# Driver4RackV3_9.net
KiCad netlist of a schematic drawn in Altium Designer
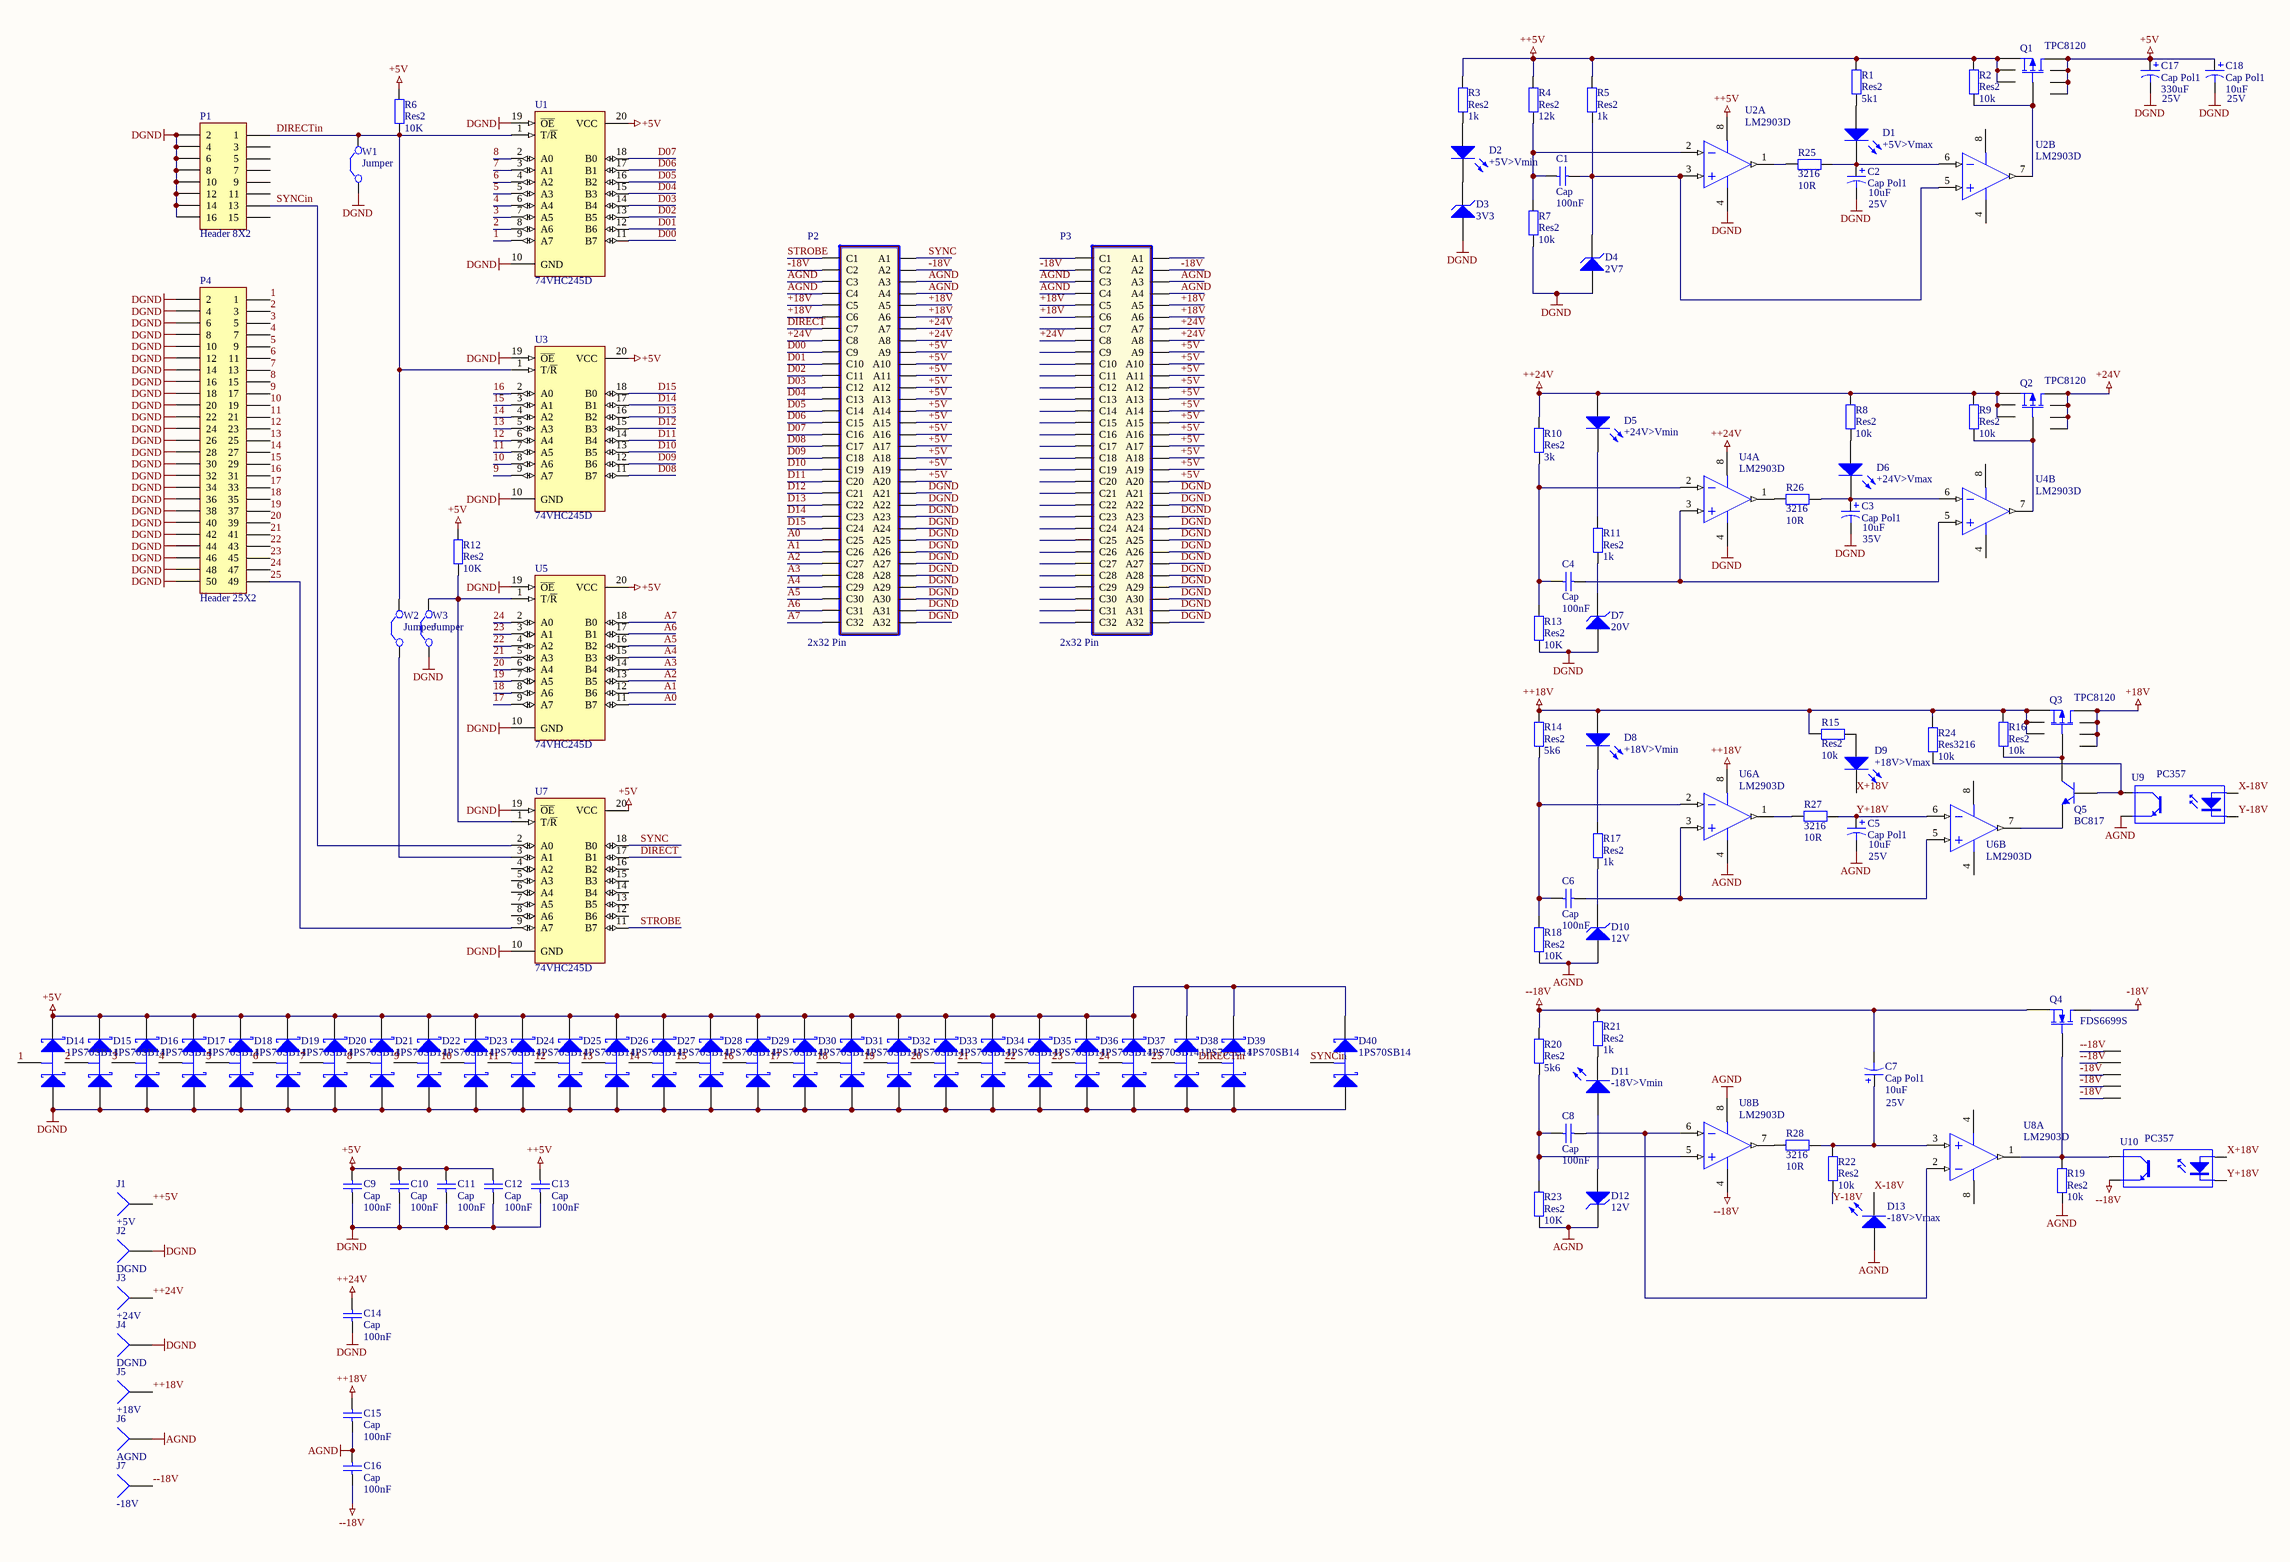
[diagram p0: Driver4RackV3.9.SchDoc]

(export (version "E")
  (design (tool "Eeschema 10.0.6"))
  (components
    (comp (ref "C1")
      (value "Cap")
      (footprint "CAPC3216M")
      (description "Capacitor")
      (fields
        (field (name "ALTIUM_VALUE") "100nF")
        (field (name "VOLTAGE") "50V")
        (field (name "PUBLISHER") "Altium Limited")
      )
      (libsource (lib "Miscellaneous Devices") (part "Cap"))
    )
    (comp (ref "C2")
      (value "Cap Pol1")
      (footprint "TC3528-1411")
      (description "Polarized Capacitor (Radial)")
      (fields
        (field (name "ALTIUM_VALUE") "10uF")
        (field (name "VOLTAGE") "25V")
        (field (name "PUBLISHER") "Altium Limited")
      )
      (libsource (lib "Miscellaneous Devices") (part "Cap Pol1"))
    )
    (comp (ref "C3")
      (value "Cap Pol1")
      (footprint "TC6032-2412")
      (description "Polarized Capacitor (Radial)")
      (fields
        (field (name "ALTIUM_VALUE") "10uF")
        (field (name "VOLTAGE") "35V")
        (field (name "PUBLISHER") "Altium Limited")
      )
      (libsource (lib "Miscellaneous Devices") (part "Cap Pol1"))
    )
    (comp (ref "C4")
      (value "Cap")
      (footprint "CAPC3216M")
      (description "Capacitor")
      (fields
        (field (name "ALTIUM_VALUE") "100nF")
        (field (name "VOLTAGE") "50V")
        (field (name "PUBLISHER") "Altium Limited")
      )
      (libsource (lib "Miscellaneous Devices") (part "Cap"))
    )
    (comp (ref "C5")
      (value "Cap Pol1")
      (footprint "TC3528-1411")
      (description "Polarized Capacitor (Radial)")
      (fields
        (field (name "ALTIUM_VALUE") "10uF")
        (field (name "VOLTAGE") "25V")
        (field (name "PUBLISHER") "Altium Limited")
      )
      (libsource (lib "Miscellaneous Devices") (part "Cap Pol1"))
    )
    (comp (ref "C6")
      (value "Cap")
      (footprint "CAPC3216M")
      (description "Capacitor")
      (fields
        (field (name "ALTIUM_VALUE") "100nF")
        (field (name "VOLTAGE") "50V")
        (field (name "PUBLISHER") "Altium Limited")
      )
      (libsource (lib "Miscellaneous Devices") (part "Cap"))
    )
    (comp (ref "C7")
      (value "Cap Pol1")
      (footprint "TC3528-1411")
      (description "Polarized Capacitor (Radial)")
      (fields
        (field (name "ALTIUM_VALUE") "10uF")
        (field (name "VOLTAGE") "25V")
        (field (name "PUBLISHER") "Altium Limited")
      )
      (libsource (lib "Miscellaneous Devices") (part "Cap Pol1"))
    )
    (comp (ref "C8")
      (value "Cap")
      (footprint "CAPC3216M")
      (description "Capacitor")
      (fields
        (field (name "ALTIUM_VALUE") "100nF")
        (field (name "VOLTAGE") "50V")
        (field (name "PUBLISHER") "Altium Limited")
      )
      (libsource (lib "Miscellaneous Devices") (part "Cap"))
    )
    (comp (ref "C9")
      (value "Cap")
      (footprint "CAPC3216M")
      (description "Capacitor")
      (fields
        (field (name "ALTIUM_VALUE") "100nF")
        (field (name "VOLTAGE") "50V")
        (field (name "PUBLISHER") "Altium Limited")
      )
      (libsource (lib "Miscellaneous Devices") (part "Cap"))
    )
    (comp (ref "C10")
      (value "Cap")
      (footprint "CAPC3216M")
      (description "Capacitor")
      (fields
        (field (name "ALTIUM_VALUE") "100nF")
        (field (name "VOLTAGE") "50V")
        (field (name "PUBLISHER") "Altium Limited")
      )
      (libsource (lib "Miscellaneous Devices") (part "Cap"))
    )
    (comp (ref "C11")
      (value "Cap")
      (footprint "CAPC3216M")
      (description "Capacitor")
      (fields
        (field (name "ALTIUM_VALUE") "100nF")
        (field (name "VOLTAGE") "50V")
        (field (name "PUBLISHER") "Altium Limited")
      )
      (libsource (lib "Miscellaneous Devices") (part "Cap"))
    )
    (comp (ref "C12")
      (value "Cap")
      (footprint "CAPC3216M")
      (description "Capacitor")
      (fields
        (field (name "ALTIUM_VALUE") "100nF")
        (field (name "VOLTAGE") "50V")
        (field (name "PUBLISHER") "Altium Limited")
      )
      (libsource (lib "Miscellaneous Devices") (part "Cap"))
    )
    (comp (ref "C13")
      (value "Cap")
      (footprint "CAPC3216M")
      (description "Capacitor")
      (fields
        (field (name "ALTIUM_VALUE") "100nF")
        (field (name "VOLTAGE") "50V")
        (field (name "PUBLISHER") "Altium Limited")
      )
      (libsource (lib "Miscellaneous Devices") (part "Cap"))
    )
    (comp (ref "C14")
      (value "Cap")
      (footprint "CAPC3216M")
      (description "Capacitor")
      (fields
        (field (name "ALTIUM_VALUE") "100nF")
        (field (name "VOLTAGE") "50V")
        (field (name "PUBLISHER") "Altium Limited")
      )
      (libsource (lib "Miscellaneous Devices") (part "Cap"))
    )
    (comp (ref "C15")
      (value "Cap")
      (footprint "CAPC3216M")
      (description "Capacitor")
      (fields
        (field (name "ALTIUM_VALUE") "100nF")
        (field (name "VOLTAGE") "50V")
        (field (name "PUBLISHER") "Altium Limited")
      )
      (libsource (lib "Miscellaneous Devices") (part "Cap"))
    )
    (comp (ref "C16")
      (value "Cap")
      (footprint "CAPC3216M")
      (description "Capacitor")
      (fields
        (field (name "ALTIUM_VALUE") "100nF")
        (field (name "VOLTAGE") "50V")
        (field (name "PUBLISHER") "Altium Limited")
      )
      (libsource (lib "Miscellaneous Devices") (part "Cap"))
    )
    (comp (ref "C17")
      (value "Cap Pol1")
      (footprint "ElkoSMD8")
      (description "Polarized Capacitor (Radial)")
      (fields
        (field (name "ALTIUM_VALUE") "330uF")
        (field (name "VOLTAGE") "25V")
        (field (name "PUBLISHER") "Altium Limited")
      )
      (libsource (lib "Miscellaneous Devices") (part "Cap Pol1"))
    )
    (comp (ref "C18")
      (value "Cap Pol1")
      (footprint "TC3528-1411")
      (description "Polarized Capacitor (Radial)")
      (fields
        (field (name "ALTIUM_VALUE") "10uF")
        (field (name "VOLTAGE") "25V")
        (field (name "PUBLISHER") "Altium Limited")
      )
      (libsource (lib "Miscellaneous Devices") (part "Cap Pol1"))
    )
    (comp (ref "D1")
      (value "+5V>Vmax")
      (footprint "3.5X2.8X1.9")
      (description "Typical RED GaAs LED")
      (fields (field (name "PUBLISHER") "Altium Limited"))
      (libsource (lib "Miscellaneous Devices") (part "LED1"))
    )
    (comp (ref "D2")
      (value "+5V>Vmin")
      (footprint "3.5X2.8X1.9")
      (description "Typical green SiC LED")
      (fields (field (name "PUBLISHER") "Altium Limited"))
      (libsource (lib "Miscellaneous Devices") (part "LED3"))
    )
    (comp (ref "D3")
      (value "3V3")
      (footprint "sod80c")
      (description "Zener Diode")
      (fields (field (name "PUBLISHER") "Altium Limited"))
      (libsource (lib "Miscellaneous Devices") (part "D Zener"))
    )
    (comp (ref "D4")
      (value "2V7")
      (footprint "sod80c")
      (description "Zener Diode")
      (fields (field (name "PUBLISHER") "Altium Limited"))
      (libsource (lib "Miscellaneous Devices") (part "D Zener"))
    )
    (comp (ref "D5")
      (value "+24V>Vmin")
      (footprint "3.5X2.8X1.9")
      (description "Typical green GaAs LED")
      (fields (field (name "PUBLISHER") "Altium Limited"))
      (libsource (lib "Miscellaneous Devices") (part "LED1"))
    )
    (comp (ref "D6")
      (value "+24V>Vmax")
      (footprint "3.5X2.8X1.9")
      (description "Typical RED GaAs LED")
      (fields (field (name "PUBLISHER") "Altium Limited"))
      (libsource (lib "Miscellaneous Devices") (part "LED1"))
    )
    (comp (ref "D7")
      (value "20V")
      (footprint "sod80c")
      (description "Zener Diode")
      (fields (field (name "PUBLISHER") "Altium Limited"))
      (libsource (lib "Miscellaneous Devices") (part "D Zener"))
    )
    (comp (ref "D8")
      (value "+18V>Vmin")
      (footprint "3.5X2.8X1.9")
      (description "Typical green GaAs LED")
      (fields (field (name "PUBLISHER") "Altium Limited"))
      (libsource (lib "Miscellaneous Devices") (part "LED1"))
    )
    (comp (ref "D9")
      (value "+18V>Vmax")
      (footprint "3.5X2.8X1.9")
      (description "Typical RED GaAs LED")
      (fields (field (name "PUBLISHER") "Altium Limited"))
      (libsource (lib "Miscellaneous Devices") (part "LED1"))
    )
    (comp (ref "D10")
      (value "12V")
      (footprint "sod80c")
      (description "Zener Diode")
      (fields (field (name "PUBLISHER") "Altium Limited"))
      (libsource (lib "Miscellaneous Devices") (part "D Zener"))
    )
    (comp (ref "D11")
      (value "-18V>Vmin")
      (footprint "3.5X2.8X1.9")
      (description "Typical green GaAs LED")
      (fields (field (name "PUBLISHER") "Altium Limited"))
      (libsource (lib "Miscellaneous Devices") (part "LED1"))
    )
    (comp (ref "D12")
      (value "12V")
      (footprint "sod80c")
      (description "Zener Diode")
      (fields (field (name "PUBLISHER") "Altium Limited"))
      (libsource (lib "Miscellaneous Devices") (part "D Zener"))
    )
    (comp (ref "D13")
      (value "-18V>Vmax")
      (footprint "3.5X2.8X1.9")
      (description "Typical RED GaAs LED")
      (fields (field (name "PUBLISHER") "Altium Limited"))
      (libsource (lib "Miscellaneous Devices") (part "LED1"))
    )
    (comp (ref "D14")
      (value "1PS70SB14")
      (footprint "SOT323")
      (description "Schottky Barrier Double Diode")
      (fields (field (name "PUBLISHER") "Altium Limited"))
      (libsource (lib "Philips Discrete Diode - Schottky") (part "1PS70SB14"))
    )
    (comp (ref "D15")
      (value "1PS70SB14")
      (footprint "SOT323")
      (description "Schottky Barrier Double Diode")
      (fields (field (name "PUBLISHER") "Altium Limited"))
      (libsource (lib "Philips Discrete Diode - Schottky") (part "1PS70SB14"))
    )
    (comp (ref "D16")
      (value "1PS70SB14")
      (footprint "SOT323")
      (description "Schottky Barrier Double Diode")
      (fields (field (name "PUBLISHER") "Altium Limited"))
      (libsource (lib "Philips Discrete Diode - Schottky") (part "1PS70SB14"))
    )
    (comp (ref "D17")
      (value "1PS70SB14")
      (footprint "SOT323")
      (description "Schottky Barrier Double Diode")
      (fields (field (name "PUBLISHER") "Altium Limited"))
      (libsource (lib "Philips Discrete Diode - Schottky") (part "1PS70SB14"))
    )
    (comp (ref "D18")
      (value "1PS70SB14")
      (footprint "SOT323")
      (description "Schottky Barrier Double Diode")
      (fields (field (name "PUBLISHER") "Altium Limited"))
      (libsource (lib "Philips Discrete Diode - Schottky") (part "1PS70SB14"))
    )
    (comp (ref "D19")
      (value "1PS70SB14")
      (footprint "SOT323")
      (description "Schottky Barrier Double Diode")
      (fields (field (name "PUBLISHER") "Altium Limited"))
      (libsource (lib "Philips Discrete Diode - Schottky") (part "1PS70SB14"))
    )
    (comp (ref "D20")
      (value "1PS70SB14")
      (footprint "SOT323")
      (description "Schottky Barrier Double Diode")
      (fields (field (name "PUBLISHER") "Altium Limited"))
      (libsource (lib "Philips Discrete Diode - Schottky") (part "1PS70SB14"))
    )
    (comp (ref "D21")
      (value "1PS70SB14")
      (footprint "SOT323")
      (description "Schottky Barrier Double Diode")
      (fields (field (name "PUBLISHER") "Altium Limited"))
      (libsource (lib "Philips Discrete Diode - Schottky") (part "1PS70SB14"))
    )
    (comp (ref "D22")
      (value "1PS70SB14")
      (footprint "SOT323")
      (description "Schottky Barrier Double Diode")
      (fields (field (name "PUBLISHER") "Altium Limited"))
      (libsource (lib "Philips Discrete Diode - Schottky") (part "1PS70SB14"))
    )
    (comp (ref "D23")
      (value "1PS70SB14")
      (footprint "SOT323")
      (description "Schottky Barrier Double Diode")
      (fields (field (name "PUBLISHER") "Altium Limited"))
      (libsource (lib "Philips Discrete Diode - Schottky") (part "1PS70SB14"))
    )
    (comp (ref "D24")
      (value "1PS70SB14")
      (footprint "SOT323")
      (description "Schottky Barrier Double Diode")
      (fields (field (name "PUBLISHER") "Altium Limited"))
      (libsource (lib "Philips Discrete Diode - Schottky") (part "1PS70SB14"))
    )
    (comp (ref "D25")
      (value "1PS70SB14")
      (footprint "SOT323")
      (description "Schottky Barrier Double Diode")
      (fields (field (name "PUBLISHER") "Altium Limited"))
      (libsource (lib "Philips Discrete Diode - Schottky") (part "1PS70SB14"))
    )
    (comp (ref "D26")
      (value "1PS70SB14")
      (footprint "SOT323")
      (description "Schottky Barrier Double Diode")
      (fields (field (name "PUBLISHER") "Altium Limited"))
      (libsource (lib "Philips Discrete Diode - Schottky") (part "1PS70SB14"))
    )
    (comp (ref "D27")
      (value "1PS70SB14")
      (footprint "SOT323")
      (description "Schottky Barrier Double Diode")
      (fields (field (name "PUBLISHER") "Altium Limited"))
      (libsource (lib "Philips Discrete Diode - Schottky") (part "1PS70SB14"))
    )
    (comp (ref "D28")
      (value "1PS70SB14")
      (footprint "SOT323")
      (description "Schottky Barrier Double Diode")
      (fields (field (name "PUBLISHER") "Altium Limited"))
      (libsource (lib "Philips Discrete Diode - Schottky") (part "1PS70SB14"))
    )
    (comp (ref "D29")
      (value "1PS70SB14")
      (footprint "SOT323")
      (description "Schottky Barrier Double Diode")
      (fields (field (name "PUBLISHER") "Altium Limited"))
      (libsource (lib "Philips Discrete Diode - Schottky") (part "1PS70SB14"))
    )
    (comp (ref "D30")
      (value "1PS70SB14")
      (footprint "SOT323")
      (description "Schottky Barrier Double Diode")
      (fields (field (name "PUBLISHER") "Altium Limited"))
      (libsource (lib "Philips Discrete Diode - Schottky") (part "1PS70SB14"))
    )
    (comp (ref "D31")
      (value "1PS70SB14")
      (footprint "SOT323")
      (description "Schottky Barrier Double Diode")
      (fields (field (name "PUBLISHER") "Altium Limited"))
      (libsource (lib "Philips Discrete Diode - Schottky") (part "1PS70SB14"))
    )
    (comp (ref "D32")
      (value "1PS70SB14")
      (footprint "SOT323")
      (description "Schottky Barrier Double Diode")
      (fields (field (name "PUBLISHER") "Altium Limited"))
      (libsource (lib "Philips Discrete Diode - Schottky") (part "1PS70SB14"))
    )
    (comp (ref "D33")
      (value "1PS70SB14")
      (footprint "SOT323")
      (description "Schottky Barrier Double Diode")
      (fields (field (name "PUBLISHER") "Altium Limited"))
      (libsource (lib "Philips Discrete Diode - Schottky") (part "1PS70SB14"))
    )
    (comp (ref "D34")
      (value "1PS70SB14")
      (footprint "SOT323")
      (description "Schottky Barrier Double Diode")
      (fields (field (name "PUBLISHER") "Altium Limited"))
      (libsource (lib "Philips Discrete Diode - Schottky") (part "1PS70SB14"))
    )
    (comp (ref "D35")
      (value "1PS70SB14")
      (footprint "SOT323")
      (description "Schottky Barrier Double Diode")
      (fields (field (name "PUBLISHER") "Altium Limited"))
      (libsource (lib "Philips Discrete Diode - Schottky") (part "1PS70SB14"))
    )
    (comp (ref "D36")
      (value "1PS70SB14")
      (footprint "SOT323")
      (description "Schottky Barrier Double Diode")
      (fields (field (name "PUBLISHER") "Altium Limited"))
      (libsource (lib "Philips Discrete Diode - Schottky") (part "1PS70SB14"))
    )
    (comp (ref "D37")
      (value "1PS70SB14")
      (footprint "SOT323")
      (description "Schottky Barrier Double Diode")
      (fields (field (name "PUBLISHER") "Altium Limited"))
      (libsource (lib "Philips Discrete Diode - Schottky") (part "1PS70SB14"))
    )
    (comp (ref "D38")
      (value "1PS70SB14")
      (footprint "SOT323")
      (description "Schottky Barrier Double Diode")
      (fields (field (name "PUBLISHER") "Altium Limited"))
      (libsource (lib "Philips Discrete Diode - Schottky") (part "1PS70SB14"))
    )
    (comp (ref "D39")
      (value "1PS70SB14")
      (footprint "SOT323")
      (description "Schottky Barrier Double Diode")
      (fields (field (name "PUBLISHER") "Altium Limited"))
      (libsource (lib "Philips Discrete Diode - Schottky") (part "1PS70SB14"))
    )
    (comp (ref "D40")
      (value "1PS70SB14")
      (footprint "SOT323")
      (description "Schottky Barrier Double Diode")
      (fields (field (name "PUBLISHER") "Altium Limited"))
      (libsource (lib "Philips Discrete Diode - Schottky") (part "1PS70SB14"))
    )
    (comp (ref "J1")
      (value "+5V")
      (footprint "PIN1")
      (description "Socket")
      (fields (field (name "PUBLISHER") "Altium Limited"))
      (libsource (lib "Miscellaneous Connectors") (part "Socket"))
    )
    (comp (ref "J2")
      (value "DGND")
      (footprint "PIN1")
      (description "Socket")
      (fields (field (name "PUBLISHER") "Altium Limited"))
      (libsource (lib "Miscellaneous Connectors") (part "Socket"))
    )
    (comp (ref "J3")
      (value "+24V")
      (footprint "PIN1")
      (description "Socket")
      (fields (field (name "PUBLISHER") "Altium Limited"))
      (libsource (lib "Miscellaneous Connectors") (part "Socket"))
    )
    (comp (ref "J4")
      (value "DGND")
      (footprint "PIN1")
      (description "Socket")
      (fields (field (name "PUBLISHER") "Altium Limited"))
      (libsource (lib "Miscellaneous Connectors") (part "Socket"))
    )
    (comp (ref "J5")
      (value "+18V")
      (footprint "PIN1")
      (description "Socket")
      (fields (field (name "PUBLISHER") "Altium Limited"))
      (libsource (lib "Miscellaneous Connectors") (part "Socket"))
    )
    (comp (ref "J6")
      (value "AGND")
      (footprint "PIN1")
      (description "Socket")
      (fields (field (name "PUBLISHER") "Altium Limited"))
      (libsource (lib "Miscellaneous Connectors") (part "Socket"))
    )
    (comp (ref "J7")
      (value "-18V")
      (footprint "PIN1")
      (description "Socket")
      (fields (field (name "PUBLISHER") "Altium Limited"))
      (libsource (lib "Miscellaneous Connectors") (part "Socket"))
    )
    (comp (ref "P1")
      (value "Header 8X2")
      (footprint "HDR2X8")
      (description "Header, 8-Pin, Dual row")
      (fields (field (name "PUBLISHER") "Altium Limited"))
      (libsource (lib "Miscellaneous Connectors") (part "Header 8X2"))
    )
    (comp (ref "P2")
      (value "2x32 Pin")
      (footprint "0903164x922")
      (description "DIN 41612")
      (libsource (lib "GeneralParts") (part "64 Pin Header"))
    )
    (comp (ref "P3")
      (value "2x32 Pin")
      (footprint "0903164x922")
      (description "DIN 41612")
      (libsource (lib "GeneralParts") (part "64 Pin Header"))
    )
    (comp (ref "P4")
      (value "Header 25X2")
      (footprint "HDR2X25")
      (description "Header, 25-Pin, Dual row")
      (fields (field (name "PUBLISHER") "Altium Limited"))
      (libsource (lib "Miscellaneous Connectors") (part "Header 25X2"))
    )
    (comp (ref "Q1")
      (value "TPC8120")
      (footprint "2-6J1B")
      (description "Mosfet P")
      (libsource (lib "eigene") (part "TPC8120"))
    )
    (comp (ref "Q2")
      (value "TPC8120")
      (footprint "2-6J1B")
      (description "Mosfet P")
      (libsource (lib "eigene") (part "TPC8120"))
    )
    (comp (ref "Q3")
      (value "TPC8120")
      (footprint "2-6J1B")
      (description "Mosfet P")
      (libsource (lib "eigene") (part "TPC8120"))
    )
    (comp (ref "Q4")
      (value "FDS6699S")
      (footprint "SO-8_M")
      (description "N-Channel MOSFET")
      (fields (field (name "PUBLISHER") "Altium Limited"))
      (libsource (lib "Miscellaneous Devices") (part "MOSFET-N"))
    )
    (comp (ref "Q5")
      (value "BC817")
      (footprint "SOT-23B_N")
      (description "NPN Bipolar Transistor")
      (fields (field (name "PUBLISHER") "Altium Limited"))
      (libsource (lib "Miscellaneous Devices") (part "QNPN"))
    )
    (comp (ref "R1")
      (value "Res2")
      (footprint "RESC3216M")
      (description "Resistor")
      (fields (field (name "ALTIUM_VALUE") "5k1") (field (name "PUBLISHER") "Altium Limited"))
      (libsource (lib "Miscellaneous Devices") (part "Res2"))
    )
    (comp (ref "R2")
      (value "Res2")
      (footprint "RESC3216M")
      (description "Resistor")
      (fields (field (name "ALTIUM_VALUE") "10k") (field (name "PUBLISHER") "Altium Limited"))
      (libsource (lib "Miscellaneous Devices") (part "Res2"))
    )
    (comp (ref "R3")
      (value "Res2")
      (footprint "RESC3216M")
      (description "Resistor")
      (fields (field (name "ALTIUM_VALUE") "1k") (field (name "PUBLISHER") "Altium Limited"))
      (libsource (lib "Miscellaneous Devices") (part "Res2"))
    )
    (comp (ref "R4")
      (value "Res2")
      (footprint "RESC3216M")
      (description "Resistor")
      (fields (field (name "ALTIUM_VALUE") "12k") (field (name "PUBLISHER") "Altium Limited"))
      (libsource (lib "Miscellaneous Devices") (part "Res2"))
    )
    (comp (ref "R5")
      (value "Res2")
      (footprint "RESC3216M")
      (description "Resistor")
      (fields (field (name "ALTIUM_VALUE") "1k") (field (name "PUBLISHER") "Altium Limited"))
      (libsource (lib "Miscellaneous Devices") (part "Res2"))
    )
    (comp (ref "R6")
      (value "Res2")
      (footprint "RESC3216M")
      (description "Resistor")
      (fields (field (name "ALTIUM_VALUE") "10K") (field (name "PUBLISHER") "Altium Limited"))
      (libsource (lib "") (part "Res2_1"))
    )
    (comp (ref "R7")
      (value "Res2")
      (footprint "RESC3216M")
      (description "Resistor")
      (fields (field (name "ALTIUM_VALUE") "10k") (field (name "PUBLISHER") "Altium Limited"))
      (libsource (lib "Miscellaneous Devices") (part "Res2"))
    )
    (comp (ref "R8")
      (value "Res2")
      (footprint "RESC3216M")
      (description "Resistor")
      (fields (field (name "ALTIUM_VALUE") "10k") (field (name "PUBLISHER") "Altium Limited"))
      (libsource (lib "Miscellaneous Devices") (part "Res2"))
    )
    (comp (ref "R9")
      (value "Res2")
      (footprint "RESC3216M")
      (description "Resistor")
      (fields (field (name "ALTIUM_VALUE") "10k") (field (name "PUBLISHER") "Altium Limited"))
      (libsource (lib "Miscellaneous Devices") (part "Res2"))
    )
    (comp (ref "R10")
      (value "Res2")
      (footprint "RESC3216M")
      (description "Resistor")
      (fields (field (name "ALTIUM_VALUE") "3k") (field (name "PUBLISHER") "Altium Limited"))
      (libsource (lib "Miscellaneous Devices") (part "Res2"))
    )
    (comp (ref "R11")
      (value "Res2")
      (footprint "RESC3216M")
      (description "Resistor")
      (fields (field (name "ALTIUM_VALUE") "1k") (field (name "PUBLISHER") "Altium Limited"))
      (libsource (lib "Miscellaneous Devices") (part "Res2"))
    )
    (comp (ref "R12")
      (value "Res2")
      (footprint "RESC3216M")
      (description "Resistor")
      (fields (field (name "ALTIUM_VALUE") "10K") (field (name "PUBLISHER") "Altium Limited"))
      (libsource (lib "") (part "Res2_1"))
    )
    (comp (ref "R13")
      (value "Res2")
      (footprint "RESC3216M")
      (description "Resistor")
      (fields (field (name "ALTIUM_VALUE") "10K") (field (name "PUBLISHER") "Altium Limited"))
      (libsource (lib "Miscellaneous Devices") (part "Res2"))
    )
    (comp (ref "R14")
      (value "Res2")
      (footprint "RESC3216M")
      (description "Resistor")
      (fields (field (name "ALTIUM_VALUE") "5k6") (field (name "PUBLISHER") "Altium Limited"))
      (libsource (lib "Miscellaneous Devices") (part "Res2"))
    )
    (comp (ref "R15")
      (value "Res2")
      (footprint "RESC3216M")
      (description "Resistor")
      (fields (field (name "ALTIUM_VALUE") "10k") (field (name "PUBLISHER") "Altium Limited"))
      (libsource (lib "") (part "Res2_2"))
    )
    (comp (ref "R16")
      (value "Res2")
      (footprint "RESC3216M")
      (description "Resistor")
      (fields (field (name "ALTIUM_VALUE") "10k") (field (name "PUBLISHER") "Altium Limited"))
      (libsource (lib "Miscellaneous Devices") (part "Res2"))
    )
    (comp (ref "R17")
      (value "Res2")
      (footprint "RESC3216M")
      (description "Resistor")
      (fields (field (name "ALTIUM_VALUE") "1k") (field (name "PUBLISHER") "Altium Limited"))
      (libsource (lib "") (part "Res2_3"))
    )
    (comp (ref "R18")
      (value "Res2")
      (footprint "RESC3216M")
      (description "Resistor")
      (fields (field (name "ALTIUM_VALUE") "10K") (field (name "PUBLISHER") "Altium Limited"))
      (libsource (lib "Miscellaneous Devices") (part "Res2"))
    )
    (comp (ref "R19")
      (value "Res2")
      (footprint "RESC3216M")
      (description "Resistor")
      (fields (field (name "ALTIUM_VALUE") "10k") (field (name "PUBLISHER") "Altium Limited"))
      (libsource (lib "Miscellaneous Devices") (part "Res2"))
    )
    (comp (ref "R20")
      (value "Res2")
      (footprint "RESC3216M")
      (description "Resistor")
      (fields (field (name "ALTIUM_VALUE") "5k6") (field (name "PUBLISHER") "Altium Limited"))
      (libsource (lib "Miscellaneous Devices") (part "Res2"))
    )
    (comp (ref "R21")
      (value "Res2")
      (footprint "RESC3216M")
      (description "Resistor")
      (fields (field (name "ALTIUM_VALUE") "1k") (field (name "PUBLISHER") "Altium Limited"))
      (libsource (lib "") (part "Res2_3"))
    )
    (comp (ref "R22")
      (value "Res2")
      (footprint "RESC3216M")
      (description "Resistor")
      (fields (field (name "ALTIUM_VALUE") "10k") (field (name "PUBLISHER") "Altium Limited"))
      (libsource (lib "Miscellaneous Devices") (part "Res2"))
    )
    (comp (ref "R23")
      (value "Res2")
      (footprint "RESC3216M")
      (description "Resistor")
      (fields (field (name "ALTIUM_VALUE") "10K") (field (name "PUBLISHER") "Altium Limited"))
      (libsource (lib "Miscellaneous Devices") (part "Res2"))
    )
    (comp (ref "R24")
      (value "Res3216")
      (footprint "RESC3216M")
      (description "Resistor")
      (fields (field (name "ALTIUM_VALUE") "10k") (field (name "PUBLISHER") "Altium Limited"))
      (libsource (lib "") (part "Resistor3216_1"))
    )
    (comp (ref "R25")
      (value "3216")
      (footprint "RESC3216M")
      (description "Resistor")
      (fields (field (name "ALTIUM_VALUE") "10R") (field (name "PUBLISHER") "Altium Limited"))
      (libsource (lib "eigene") (part "Resistor3216"))
    )
    (comp (ref "R26")
      (value "3216")
      (footprint "RESC3216M")
      (description "Resistor")
      (fields (field (name "ALTIUM_VALUE") "10R") (field (name "PUBLISHER") "Altium Limited"))
      (libsource (lib "eigene") (part "Resistor3216"))
    )
    (comp (ref "R27")
      (value "3216")
      (footprint "RESC3216M")
      (description "Resistor")
      (fields (field (name "ALTIUM_VALUE") "10R") (field (name "PUBLISHER") "Altium Limited"))
      (libsource (lib "eigene") (part "Resistor3216"))
    )
    (comp (ref "R28")
      (value "3216")
      (footprint "RESC3216M")
      (description "Resistor")
      (fields (field (name "ALTIUM_VALUE") "10R") (field (name "PUBLISHER") "Altium Limited"))
      (libsource (lib "eigene") (part "Resistor3216"))
    )
    (comp (ref "U1")
      (value "74VHC245D")
      (footprint "DW020_N")
      (description "Octal Bus Transceiver with 3-State Outputs")
      (fields (field (name "PUBLISHER") "Altium Limited"))
      (libsource (lib "TI Interface 8-Bit Line Transceiver") (part "SN74HC245DW"))
    )
    (comp (ref "U2")
      (value "LM2903D")
      (footprint "751-02_N")
      (description "Dual Comparator")
      (fields (field (name "PUBLISHER") "Altium Limited"))
      (libsource (lib "Motorola Analog Comparator") (part "LM2903D"))
    )
    (comp (ref "U3")
      (value "74VHC245D")
      (footprint "DW020_N")
      (description "Octal Bus Transceiver with 3-State Outputs")
      (fields (field (name "PUBLISHER") "Altium Limited"))
      (libsource (lib "TI Interface 8-Bit Line Transceiver") (part "SN74HC245DW"))
    )
    (comp (ref "U4")
      (value "LM2903D")
      (footprint "751-02_N")
      (description "Dual Comparator")
      (fields (field (name "PUBLISHER") "Altium Limited"))
      (libsource (lib "Motorola Analog Comparator") (part "LM2903D"))
    )
    (comp (ref "U5")
      (value "74VHC245D")
      (footprint "DW020_N")
      (description "Octal Bus Transceiver with 3-State Outputs")
      (fields (field (name "PUBLISHER") "Altium Limited"))
      (libsource (lib "TI Interface 8-Bit Line Transceiver") (part "SN74HC245DW"))
    )
    (comp (ref "U6")
      (value "LM2903D")
      (footprint "751-02_N")
      (description "Dual Comparator")
      (fields (field (name "PUBLISHER") "Altium Limited"))
      (libsource (lib "Motorola Analog Comparator") (part "LM2903D"))
    )
    (comp (ref "U7")
      (value "74VHC245D")
      (footprint "DW020_N")
      (description "Octal Bus Transceiver with 3-State Outputs")
      (fields (field (name "PUBLISHER") "Altium Limited"))
      (libsource (lib "TI Interface 8-Bit Line Transceiver") (part "SN74HC245DW"))
    )
    (comp (ref "U8")
      (value "LM2903D")
      (footprint "751-02_N")
      (description "Dual Comparator")
      (fields (field (name "PUBLISHER") "Altium Limited"))
      (libsource (lib "Motorola Analog Comparator") (part "LM2903D"))
    )
    (comp (ref "U9")
      (value "PC357")
      (footprint "PC357NJ")
      (description "4-Pin Phototransistor Optocoupler")
      (fields (field (name "PUBLISHER") "Altium Limited"))
      (libsource (lib "Miscellaneous Devices") (part "Optoisolator1"))
    )
    (comp (ref "U10")
      (value "PC357")
      (footprint "PC357NJ")
      (description "4-Pin Phototransistor Optocoupler")
      (fields (field (name "PUBLISHER") "Altium Limited"))
      (libsource (lib "Miscellaneous Devices") (part "Optoisolator1"))
    )
    (comp (ref "W1")
      (value "Jumper")
      (footprint "RAD-0.1")
      (description "Jumper Wire")
      (fields (field (name "PUBLISHER") "Altium Limited"))
      (libsource (lib "Miscellaneous Devices") (part "Jumper"))
    )
    (comp (ref "W2")
      (value "Jumper")
      (footprint "RAD-0.1")
      (description "Jumper Wire")
      (fields (field (name "PUBLISHER") "Altium Limited"))
      (libsource (lib "Miscellaneous Devices") (part "Jumper"))
    )
    (comp (ref "W3")
      (value "Jumper")
      (footprint "RAD-0.1")
      (description "Jumper Wire")
      (fields (field (name "PUBLISHER") "Altium Limited"))
      (libsource (lib "Miscellaneous Devices") (part "Jumper"))
    )
  )
  (nets
    (net (code "1") (name "++5V") (class "Default")
      (node (ref "C13") (pin "2") (pinfunction "2_2") (pintype "passive"))
      (node (ref "J1") (pin "1") (pinfunction "1_1") (pintype "passive"))
      (node (ref "Q1") (pin "1") (pinfunction "S_1") (pintype "passive"))
      (node (ref "Q1") (pin "2") (pinfunction "S_2") (pintype "passive"))
      (node (ref "Q1") (pin "3") (pinfunction "S_3") (pintype "passive"))
      (node (ref "R1") (pin "2") (pinfunction "2_2") (pintype "passive"))
      (node (ref "R2") (pin "2") (pinfunction "2_2") (pintype "passive"))
      (node (ref "R3") (pin "2") (pinfunction "2_2") (pintype "passive"))
      (node (ref "R4") (pin "2") (pinfunction "2_2") (pintype "passive"))
      (node (ref "R5") (pin "2") (pinfunction "2_2") (pintype "passive"))
      (node (ref "U2") (pin "8") (pinfunction "V+_8") (pintype "power_in"))
    )
    (net (code "2") (name "++18V") (class "Default")
      (node (ref "C15") (pin "2") (pinfunction "2_2") (pintype "passive"))
      (node (ref "D8") (pin "1") (pinfunction "A_1") (pintype "passive"))
      (node (ref "J5") (pin "1") (pinfunction "1_1") (pintype "passive"))
      (node (ref "Q3") (pin "1") (pinfunction "S_1") (pintype "passive"))
      (node (ref "Q3") (pin "2") (pinfunction "S_2") (pintype "passive"))
      (node (ref "Q3") (pin "3") (pinfunction "S_3") (pintype "passive"))
      (node (ref "R14") (pin "2") (pinfunction "2_2") (pintype "passive"))
      (node (ref "R15") (pin "2") (pinfunction "2_2") (pintype "passive"))
      (node (ref "R16") (pin "2") (pinfunction "2_2") (pintype "passive"))
      (node (ref "R24") (pin "1") (pinfunction "1_1") (pintype "passive"))
      (node (ref "U6") (pin "8") (pinfunction "V+_8") (pintype "power_in"))
    )
    (net (code "3") (name "++24V") (class "Default")
      (node (ref "C14") (pin "2") (pinfunction "2_2") (pintype "passive"))
      (node (ref "D5") (pin "1") (pinfunction "A_1") (pintype "passive"))
      (node (ref "J3") (pin "1") (pinfunction "1_1") (pintype "passive"))
      (node (ref "Q2") (pin "1") (pinfunction "S_1") (pintype "passive"))
      (node (ref "Q2") (pin "2") (pinfunction "S_2") (pintype "passive"))
      (node (ref "Q2") (pin "3") (pinfunction "S_3") (pintype "passive"))
      (node (ref "R10") (pin "2") (pinfunction "2_2") (pintype "passive"))
      (node (ref "R8") (pin "2") (pinfunction "2_2") (pintype "passive"))
      (node (ref "R9") (pin "2") (pinfunction "2_2") (pintype "passive"))
      (node (ref "U4") (pin "8") (pinfunction "V+_8") (pintype "power_in"))
    )
    (net (code "4") (name "+5V") (class "Default")
      (node (ref "C10") (pin "2") (pinfunction "2_2") (pintype "passive"))
      (node (ref "C11") (pin "2") (pinfunction "2_2") (pintype "passive"))
      (node (ref "C12") (pin "2") (pinfunction "2_2") (pintype "passive"))
      (node (ref "C17") (pin "1") (pinfunction "1_1") (pintype "passive"))
      (node (ref "C18") (pin "1") (pinfunction "1_1") (pintype "passive"))
      (node (ref "C9") (pin "2") (pinfunction "2_2") (pintype "passive"))
      (node (ref "D14") (pin "2") (pinfunction "K_2") (pintype "passive"))
      (node (ref "D15") (pin "2") (pinfunction "K_2") (pintype "passive"))
      (node (ref "D16") (pin "2") (pinfunction "K_2") (pintype "passive"))
      (node (ref "D17") (pin "2") (pinfunction "K_2") (pintype "passive"))
      (node (ref "D18") (pin "2") (pinfunction "K_2") (pintype "passive"))
      (node (ref "D19") (pin "2") (pinfunction "K_2") (pintype "passive"))
      (node (ref "D20") (pin "2") (pinfunction "K_2") (pintype "passive"))
      (node (ref "D21") (pin "2") (pinfunction "K_2") (pintype "passive"))
      (node (ref "D22") (pin "2") (pinfunction "K_2") (pintype "passive"))
      (node (ref "D23") (pin "2") (pinfunction "K_2") (pintype "passive"))
      (node (ref "D24") (pin "2") (pinfunction "K_2") (pintype "passive"))
      (node (ref "D25") (pin "2") (pinfunction "K_2") (pintype "passive"))
      (node (ref "D26") (pin "2") (pinfunction "K_2") (pintype "passive"))
      (node (ref "D27") (pin "2") (pinfunction "K_2") (pintype "passive"))
      (node (ref "D28") (pin "2") (pinfunction "K_2") (pintype "passive"))
      (node (ref "D29") (pin "2") (pinfunction "K_2") (pintype "passive"))
      (node (ref "D30") (pin "2") (pinfunction "K_2") (pintype "passive"))
      (node (ref "D31") (pin "2") (pinfunction "K_2") (pintype "passive"))
      (node (ref "D32") (pin "2") (pinfunction "K_2") (pintype "passive"))
      (node (ref "D33") (pin "2") (pinfunction "K_2") (pintype "passive"))
      (node (ref "D34") (pin "2") (pinfunction "K_2") (pintype "passive"))
      (node (ref "D35") (pin "2") (pinfunction "K_2") (pintype "passive"))
      (node (ref "D36") (pin "2") (pinfunction "K_2") (pintype "passive"))
      (node (ref "D37") (pin "2") (pinfunction "K_2") (pintype "passive"))
      (node (ref "D38") (pin "2") (pinfunction "K_2") (pintype "passive"))
      (node (ref "D39") (pin "2") (pinfunction "K_2") (pintype "passive"))
      (node (ref "D40") (pin "2") (pinfunction "K_2") (pintype "passive"))
      (node (ref "P2") (pin "A10") (pinfunction "A10_A10") (pintype "passive"))
      (node (ref "P2") (pin "A11") (pinfunction "A11_A11") (pintype "passive"))
      (node (ref "P2") (pin "A12") (pinfunction "A12_A12") (pintype "passive"))
      (node (ref "P2") (pin "A13") (pinfunction "A13_A13") (pintype "passive"))
      (node (ref "P2") (pin "A14") (pinfunction "A14_A14") (pintype "passive"))
      (node (ref "P2") (pin "A15") (pinfunction "A15_A15") (pintype "passive"))
      (node (ref "P2") (pin "A16") (pinfunction "A16_A16") (pintype "passive"))
      (node (ref "P2") (pin "A17") (pinfunction "A17_A17") (pintype "passive"))
      (node (ref "P2") (pin "A18") (pinfunction "A18_A18") (pintype "passive"))
      (node (ref "P2") (pin "A19") (pinfunction "A19_A19") (pintype "passive"))
      (node (ref "P2") (pin "A20") (pinfunction "A20_A20") (pintype "passive"))
      (node (ref "P2") (pin "A9") (pinfunction "A9_A9") (pintype "passive"))
      (node (ref "P3") (pin "A10") (pinfunction "A10_A10") (pintype "passive"))
      (node (ref "P3") (pin "A11") (pinfunction "A11_A11") (pintype "passive"))
      (node (ref "P3") (pin "A12") (pinfunction "A12_A12") (pintype "passive"))
      (node (ref "P3") (pin "A13") (pinfunction "A13_A13") (pintype "passive"))
      (node (ref "P3") (pin "A14") (pinfunction "A14_A14") (pintype "passive"))
      (node (ref "P3") (pin "A15") (pinfunction "A15_A15") (pintype "passive"))
      (node (ref "P3") (pin "A16") (pinfunction "A16_A16") (pintype "passive"))
      (node (ref "P3") (pin "A17") (pinfunction "A17_A17") (pintype "passive"))
      (node (ref "P3") (pin "A18") (pinfunction "A18_A18") (pintype "passive"))
      (node (ref "P3") (pin "A19") (pinfunction "A19_A19") (pintype "passive"))
      (node (ref "P3") (pin "A20") (pinfunction "A20_A20") (pintype "passive"))
      (node (ref "P3") (pin "A9") (pinfunction "A9_A9") (pintype "passive"))
      (node (ref "Q1") (pin "5") (pinfunction "D_5") (pintype "passive"))
      (node (ref "Q1") (pin "6") (pinfunction "D_6") (pintype "passive"))
      (node (ref "Q1") (pin "7") (pinfunction "D_7") (pintype "passive"))
      (node (ref "Q1") (pin "8") (pinfunction "D_8") (pintype "passive"))
      (node (ref "R12") (pin "2") (pinfunction "2_2") (pintype "passive"))
      (node (ref "R6") (pin "2") (pinfunction "2_2") (pintype "passive"))
      (node (ref "U1") (pin "20") (pinfunction "VCC_20") (pintype "power_in"))
      (node (ref "U3") (pin "20") (pinfunction "VCC_20") (pintype "power_in"))
      (node (ref "U5") (pin "20") (pinfunction "VCC_20") (pintype "power_in"))
      (node (ref "U7") (pin "20") (pinfunction "VCC_20") (pintype "power_in"))
    )
    (net (code "5") (name "+18V") (class "Default")
      (node (ref "P2") (pin "A5") (pinfunction "A5_A5") (pintype "passive"))
      (node (ref "P2") (pin "A6") (pinfunction "A6_A6") (pintype "passive"))
      (node (ref "P2") (pin "C5") (pinfunction "C5_C5") (pintype "passive"))
      (node (ref "P2") (pin "C6") (pinfunction "C6_C6") (pintype "passive"))
      (node (ref "P3") (pin "A5") (pinfunction "A5_A5") (pintype "passive"))
      (node (ref "P3") (pin "A6") (pinfunction "A6_A6") (pintype "passive"))
      (node (ref "P3") (pin "C5") (pinfunction "C5_C5") (pintype "passive"))
      (node (ref "P3") (pin "C6") (pinfunction "C6_C6") (pintype "passive"))
      (node (ref "Q3") (pin "5") (pinfunction "D_5") (pintype "passive"))
      (node (ref "Q3") (pin "6") (pinfunction "D_6") (pintype "passive"))
      (node (ref "Q3") (pin "7") (pinfunction "D_7") (pintype "passive"))
      (node (ref "Q3") (pin "8") (pinfunction "D_8") (pintype "passive"))
    )
    (net (code "6") (name "+24V") (class "Default")
      (node (ref "P2") (pin "A7") (pinfunction "A7_A7") (pintype "passive"))
      (node (ref "P2") (pin "A8") (pinfunction "A8_A8") (pintype "passive"))
      (node (ref "P2") (pin "C8") (pinfunction "C8_C8") (pintype "passive"))
      (node (ref "P3") (pin "A7") (pinfunction "A7_A7") (pintype "passive"))
      (node (ref "P3") (pin "A8") (pinfunction "A8_A8") (pintype "passive"))
      (node (ref "P3") (pin "C8") (pinfunction "C8_C8") (pintype "passive"))
      (node (ref "Q2") (pin "5") (pinfunction "D_5") (pintype "passive"))
      (node (ref "Q2") (pin "6") (pinfunction "D_6") (pintype "passive"))
      (node (ref "Q2") (pin "7") (pinfunction "D_7") (pintype "passive"))
      (node (ref "Q2") (pin "8") (pinfunction "D_8") (pintype "passive"))
    )
    (net (code "7") (name "--18V") (class "Default")
      (node (ref "C16") (pin "1") (pinfunction "1_1") (pintype "passive"))
      (node (ref "C7") (pin "2") (pinfunction "2_2") (pintype "passive"))
      (node (ref "J7") (pin "1") (pinfunction "1_1") (pintype "passive"))
      (node (ref "Q4") (pin "1") (pinfunction "S_1") (pintype "passive"))
      (node (ref "Q4") (pin "2") (pinfunction "S_2") (pintype "passive"))
      (node (ref "Q4") (pin "3") (pinfunction "S_3") (pintype "passive"))
      (node (ref "R20") (pin "2") (pinfunction "2_2") (pintype "passive"))
      (node (ref "R21") (pin "1") (pinfunction "1_1") (pintype "passive"))
      (node (ref "U10") (pin "3") (pinfunction "E_3") (pintype "passive"))
      (node (ref "U8") (pin "4") (pinfunction "GND_4") (pintype "power_in"))
    )
    (net (code "8") (name "-18V") (class "Default")
      (node (ref "P2") (pin "A2") (pinfunction "A2_A2") (pintype "passive"))
      (node (ref "P2") (pin "C2") (pinfunction "C2_C2") (pintype "passive"))
      (node (ref "P3") (pin "A2") (pinfunction "A2_A2") (pintype "passive"))
      (node (ref "P3") (pin "C2") (pinfunction "C2_C2") (pintype "passive"))
      (node (ref "Q4") (pin "5") (pinfunction "D_5") (pintype "passive"))
      (node (ref "Q4") (pin "6") (pinfunction "D_6") (pintype "passive"))
      (node (ref "Q4") (pin "7") (pinfunction "D_7") (pintype "passive"))
      (node (ref "Q4") (pin "8") (pinfunction "D_8") (pintype "passive"))
    )
    (net (code "9") (name "/1") (class "Default")
      (node (ref "D14") (pin "3") (pinfunction "C_3") (pintype "passive"))
      (node (ref "P4") (pin "1") (pinfunction "1_1") (pintype "passive"))
      (node (ref "U1") (pin "9") (pinfunction "A7_9") (pintype "bidirectional"))
    )
    (net (code "10") (name "/2") (class "Default")
      (node (ref "D15") (pin "3") (pinfunction "C_3") (pintype "passive"))
      (node (ref "P4") (pin "3") (pinfunction "3_3") (pintype "passive"))
      (node (ref "U1") (pin "8") (pinfunction "A6_8") (pintype "bidirectional"))
    )
    (net (code "11") (name "/3") (class "Default")
      (node (ref "D16") (pin "3") (pinfunction "C_3") (pintype "passive"))
      (node (ref "P4") (pin "5") (pinfunction "5_5") (pintype "passive"))
      (node (ref "U1") (pin "7") (pinfunction "A5_7") (pintype "bidirectional"))
    )
    (net (code "12") (name "/4") (class "Default")
      (node (ref "D17") (pin "3") (pinfunction "C_3") (pintype "passive"))
      (node (ref "P4") (pin "7") (pinfunction "7_7") (pintype "passive"))
      (node (ref "U1") (pin "6") (pinfunction "A4_6") (pintype "bidirectional"))
    )
    (net (code "13") (name "/5") (class "Default")
      (node (ref "D18") (pin "3") (pinfunction "C_3") (pintype "passive"))
      (node (ref "P4") (pin "9") (pinfunction "9_9") (pintype "passive"))
      (node (ref "U1") (pin "5") (pinfunction "A3_5") (pintype "bidirectional"))
    )
    (net (code "14") (name "/6") (class "Default")
      (node (ref "D19") (pin "3") (pinfunction "C_3") (pintype "passive"))
      (node (ref "P4") (pin "11") (pinfunction "11_11") (pintype "passive"))
      (node (ref "U1") (pin "4") (pinfunction "A2_4") (pintype "bidirectional"))
    )
    (net (code "15") (name "/7") (class "Default")
      (node (ref "D20") (pin "3") (pinfunction "C_3") (pintype "passive"))
      (node (ref "P4") (pin "13") (pinfunction "13_13") (pintype "passive"))
      (node (ref "U1") (pin "3") (pinfunction "A1_3") (pintype "bidirectional"))
    )
    (net (code "16") (name "/8") (class "Default")
      (node (ref "D21") (pin "3") (pinfunction "C_3") (pintype "passive"))
      (node (ref "P4") (pin "15") (pinfunction "15_15") (pintype "passive"))
      (node (ref "U1") (pin "2") (pinfunction "A0_2") (pintype "bidirectional"))
    )
    (net (code "17") (name "/9") (class "Default")
      (node (ref "D22") (pin "3") (pinfunction "C_3") (pintype "passive"))
      (node (ref "P4") (pin "17") (pinfunction "17_17") (pintype "passive"))
      (node (ref "U3") (pin "9") (pinfunction "A7_9") (pintype "bidirectional"))
    )
    (net (code "18") (name "/10") (class "Default")
      (node (ref "D23") (pin "3") (pinfunction "C_3") (pintype "passive"))
      (node (ref "P4") (pin "19") (pinfunction "19_19") (pintype "passive"))
      (node (ref "U3") (pin "8") (pinfunction "A6_8") (pintype "bidirectional"))
    )
    (net (code "19") (name "/11") (class "Default")
      (node (ref "D24") (pin "3") (pinfunction "C_3") (pintype "passive"))
      (node (ref "P4") (pin "21") (pinfunction "21_21") (pintype "passive"))
      (node (ref "U3") (pin "7") (pinfunction "A5_7") (pintype "bidirectional"))
    )
    (net (code "20") (name "/12") (class "Default")
      (node (ref "D25") (pin "3") (pinfunction "C_3") (pintype "passive"))
      (node (ref "P4") (pin "23") (pinfunction "23_23") (pintype "passive"))
      (node (ref "U3") (pin "6") (pinfunction "A4_6") (pintype "bidirectional"))
    )
    (net (code "21") (name "/13") (class "Default")
      (node (ref "D26") (pin "3") (pinfunction "C_3") (pintype "passive"))
      (node (ref "P4") (pin "25") (pinfunction "25_25") (pintype "passive"))
      (node (ref "U3") (pin "5") (pinfunction "A3_5") (pintype "bidirectional"))
    )
    (net (code "22") (name "/14") (class "Default")
      (node (ref "D27") (pin "3") (pinfunction "C_3") (pintype "passive"))
      (node (ref "P4") (pin "27") (pinfunction "27_27") (pintype "passive"))
      (node (ref "U3") (pin "4") (pinfunction "A2_4") (pintype "bidirectional"))
    )
    (net (code "23") (name "/15") (class "Default")
      (node (ref "D28") (pin "3") (pinfunction "C_3") (pintype "passive"))
      (node (ref "P4") (pin "29") (pinfunction "29_29") (pintype "passive"))
      (node (ref "U3") (pin "3") (pinfunction "A1_3") (pintype "bidirectional"))
    )
    (net (code "24") (name "/16") (class "Default")
      (node (ref "D29") (pin "3") (pinfunction "C_3") (pintype "passive"))
      (node (ref "P4") (pin "31") (pinfunction "31_31") (pintype "passive"))
      (node (ref "U3") (pin "2") (pinfunction "A0_2") (pintype "bidirectional"))
    )
    (net (code "25") (name "/17") (class "Default")
      (node (ref "D30") (pin "3") (pinfunction "C_3") (pintype "passive"))
      (node (ref "P4") (pin "33") (pinfunction "33_33") (pintype "passive"))
      (node (ref "U5") (pin "9") (pinfunction "A7_9") (pintype "bidirectional"))
    )
    (net (code "26") (name "/18") (class "Default")
      (node (ref "D31") (pin "3") (pinfunction "C_3") (pintype "passive"))
      (node (ref "P4") (pin "35") (pinfunction "35_35") (pintype "passive"))
      (node (ref "U5") (pin "8") (pinfunction "A6_8") (pintype "bidirectional"))
    )
    (net (code "27") (name "/19") (class "Default")
      (node (ref "D32") (pin "3") (pinfunction "C_3") (pintype "passive"))
      (node (ref "P4") (pin "37") (pinfunction "37_37") (pintype "passive"))
      (node (ref "U5") (pin "7") (pinfunction "A5_7") (pintype "bidirectional"))
    )
    (net (code "28") (name "/20") (class "Default")
      (node (ref "D33") (pin "3") (pinfunction "C_3") (pintype "passive"))
      (node (ref "P4") (pin "39") (pinfunction "39_39") (pintype "passive"))
      (node (ref "U5") (pin "6") (pinfunction "A4_6") (pintype "bidirectional"))
    )
    (net (code "29") (name "/21") (class "Default")
      (node (ref "D34") (pin "3") (pinfunction "C_3") (pintype "passive"))
      (node (ref "P4") (pin "41") (pinfunction "41_41") (pintype "passive"))
      (node (ref "U5") (pin "5") (pinfunction "A3_5") (pintype "bidirectional"))
    )
    (net (code "30") (name "/22") (class "Default")
      (node (ref "D35") (pin "3") (pinfunction "C_3") (pintype "passive"))
      (node (ref "P4") (pin "43") (pinfunction "43_43") (pintype "passive"))
      (node (ref "U5") (pin "4") (pinfunction "A2_4") (pintype "bidirectional"))
    )
    (net (code "31") (name "/23") (class "Default")
      (node (ref "D36") (pin "3") (pinfunction "C_3") (pintype "passive"))
      (node (ref "P4") (pin "45") (pinfunction "45_45") (pintype "passive"))
      (node (ref "U5") (pin "3") (pinfunction "A1_3") (pintype "bidirectional"))
    )
    (net (code "32") (name "/24") (class "Default")
      (node (ref "D37") (pin "3") (pinfunction "C_3") (pintype "passive"))
      (node (ref "P4") (pin "47") (pinfunction "47_47") (pintype "passive"))
      (node (ref "U5") (pin "2") (pinfunction "A0_2") (pintype "bidirectional"))
    )
    (net (code "33") (name "/25") (class "Default")
      (node (ref "D38") (pin "3") (pinfunction "C_3") (pintype "passive"))
      (node (ref "P4") (pin "49") (pinfunction "49_49") (pintype "passive"))
      (node (ref "U7") (pin "9") (pinfunction "A7_9") (pintype "bidirectional"))
    )
    (net (code "34") (name "/A0") (class "Default")
      (node (ref "P2") (pin "C25") (pinfunction "C25_C25") (pintype "passive"))
      (node (ref "U5") (pin "11") (pinfunction "B7_11") (pintype "bidirectional"))
    )
    (net (code "35") (name "/A1") (class "Default")
      (node (ref "P2") (pin "C26") (pinfunction "C26_C26") (pintype "passive"))
      (node (ref "U5") (pin "12") (pinfunction "B6_12") (pintype "bidirectional"))
    )
    (net (code "36") (name "/A2") (class "Default")
      (node (ref "P2") (pin "C27") (pinfunction "C27_C27") (pintype "passive"))
      (node (ref "U5") (pin "13") (pinfunction "B5_13") (pintype "bidirectional"))
    )
    (net (code "37") (name "/A3") (class "Default")
      (node (ref "P2") (pin "C28") (pinfunction "C28_C28") (pintype "passive"))
      (node (ref "U5") (pin "14") (pinfunction "B4_14") (pintype "bidirectional"))
    )
    (net (code "38") (name "/A4") (class "Default")
      (node (ref "P2") (pin "C29") (pinfunction "C29_C29") (pintype "passive"))
      (node (ref "U5") (pin "15") (pinfunction "B3_15") (pintype "bidirectional"))
    )
    (net (code "39") (name "/A5") (class "Default")
      (node (ref "P2") (pin "C30") (pinfunction "C30_C30") (pintype "passive"))
      (node (ref "U5") (pin "16") (pinfunction "B2_16") (pintype "bidirectional"))
    )
    (net (code "40") (name "/A6") (class "Default")
      (node (ref "P2") (pin "C31") (pinfunction "C31_C31") (pintype "passive"))
      (node (ref "U5") (pin "17") (pinfunction "B1_17") (pintype "bidirectional"))
    )
    (net (code "41") (name "/A7") (class "Default")
      (node (ref "P2") (pin "C32") (pinfunction "C32_C32") (pintype "passive"))
      (node (ref "U5") (pin "18") (pinfunction "B0_18") (pintype "bidirectional"))
    )
    (net (code "42") (name "/D00") (class "Default")
      (node (ref "P2") (pin "C9") (pinfunction "C9_C9") (pintype "passive"))
      (node (ref "U1") (pin "11") (pinfunction "B7_11") (pintype "bidirectional"))
    )
    (net (code "43") (name "/D01") (class "Default")
      (node (ref "P2") (pin "C10") (pinfunction "C10_C10") (pintype "passive"))
      (node (ref "U1") (pin "12") (pinfunction "B6_12") (pintype "bidirectional"))
    )
    (net (code "44") (name "/D02") (class "Default")
      (node (ref "P2") (pin "C11") (pinfunction "C11_C11") (pintype "passive"))
      (node (ref "U1") (pin "13") (pinfunction "B5_13") (pintype "bidirectional"))
    )
    (net (code "45") (name "/D03") (class "Default")
      (node (ref "P2") (pin "C12") (pinfunction "C12_C12") (pintype "passive"))
      (node (ref "U1") (pin "14") (pinfunction "B4_14") (pintype "bidirectional"))
    )
    (net (code "46") (name "/D04") (class "Default")
      (node (ref "P2") (pin "C13") (pinfunction "C13_C13") (pintype "passive"))
      (node (ref "U1") (pin "15") (pinfunction "B3_15") (pintype "bidirectional"))
    )
    (net (code "47") (name "/D05") (class "Default")
      (node (ref "P2") (pin "C14") (pinfunction "C14_C14") (pintype "passive"))
      (node (ref "U1") (pin "16") (pinfunction "B2_16") (pintype "bidirectional"))
    )
    (net (code "48") (name "/D06") (class "Default")
      (node (ref "P2") (pin "C15") (pinfunction "C15_C15") (pintype "passive"))
      (node (ref "U1") (pin "17") (pinfunction "B1_17") (pintype "bidirectional"))
    )
    (net (code "49") (name "/D07") (class "Default")
      (node (ref "P2") (pin "C16") (pinfunction "C16_C16") (pintype "passive"))
      (node (ref "U1") (pin "18") (pinfunction "B0_18") (pintype "bidirectional"))
    )
    (net (code "50") (name "/D08") (class "Default")
      (node (ref "P2") (pin "C17") (pinfunction "C17_C17") (pintype "passive"))
      (node (ref "U3") (pin "11") (pinfunction "B7_11") (pintype "bidirectional"))
    )
    (net (code "51") (name "/D09") (class "Default")
      (node (ref "P2") (pin "C18") (pinfunction "C18_C18") (pintype "passive"))
      (node (ref "U3") (pin "12") (pinfunction "B6_12") (pintype "bidirectional"))
    )
    (net (code "52") (name "/D10") (class "Default")
      (node (ref "P2") (pin "C19") (pinfunction "C19_C19") (pintype "passive"))
      (node (ref "U3") (pin "13") (pinfunction "B5_13") (pintype "bidirectional"))
    )
    (net (code "53") (name "/D11") (class "Default")
      (node (ref "P2") (pin "C20") (pinfunction "C20_C20") (pintype "passive"))
      (node (ref "U3") (pin "14") (pinfunction "B4_14") (pintype "bidirectional"))
    )
    (net (code "54") (name "/D12") (class "Default")
      (node (ref "P2") (pin "C21") (pinfunction "C21_C21") (pintype "passive"))
      (node (ref "U3") (pin "15") (pinfunction "B3_15") (pintype "bidirectional"))
    )
    (net (code "55") (name "/D13") (class "Default")
      (node (ref "P2") (pin "C22") (pinfunction "C22_C22") (pintype "passive"))
      (node (ref "U3") (pin "16") (pinfunction "B2_16") (pintype "bidirectional"))
    )
    (net (code "56") (name "/D14") (class "Default")
      (node (ref "P2") (pin "C23") (pinfunction "C23_C23") (pintype "passive"))
      (node (ref "U3") (pin "17") (pinfunction "B1_17") (pintype "bidirectional"))
    )
    (net (code "57") (name "/D15") (class "Default")
      (node (ref "P2") (pin "C24") (pinfunction "C24_C24") (pintype "passive"))
      (node (ref "U3") (pin "18") (pinfunction "B0_18") (pintype "bidirectional"))
    )
    (net (code "58") (name "/DIRECT") (class "Default")
      (node (ref "P2") (pin "C7") (pinfunction "C7_C7") (pintype "passive"))
      (node (ref "U7") (pin "17") (pinfunction "B1_17") (pintype "bidirectional"))
    )
    (net (code "59") (name "/DIRECTin") (class "Default")
      (node (ref "D39") (pin "3") (pinfunction "C_3") (pintype "passive"))
      (node (ref "P1") (pin "1") (pinfunction "1_1") (pintype "passive"))
      (node (ref "R6") (pin "1") (pinfunction "1_1") (pintype "passive"))
      (node (ref "U1") (pin "1") (pinfunction "T/~{R}_1") (pintype "input"))
      (node (ref "U3") (pin "1") (pinfunction "T/~{R}_1") (pintype "input"))
      (node (ref "W1") (pin "2") (pinfunction "C2_2") (pintype "passive"))
      (node (ref "W2") (pin "2") (pinfunction "C2_2") (pintype "passive"))
    )
    (net (code "60") (name "/STROBE") (class "Default")
      (node (ref "P2") (pin "C1") (pinfunction "C1_C1") (pintype "passive"))
      (node (ref "U7") (pin "11") (pinfunction "B7_11") (pintype "bidirectional"))
    )
    (net (code "61") (name "/SYNC") (class "Default")
      (node (ref "P2") (pin "A1") (pinfunction "A1_A1") (pintype "passive"))
      (node (ref "U7") (pin "18") (pinfunction "B0_18") (pintype "bidirectional"))
    )
    (net (code "62") (name "/SYNCin") (class "Default")
      (node (ref "D40") (pin "3") (pinfunction "C_3") (pintype "passive"))
      (node (ref "P1") (pin "13") (pinfunction "13_13") (pintype "passive"))
      (node (ref "U7") (pin "2") (pinfunction "A0_2") (pintype "bidirectional"))
    )
    (net (code "63") (name "/X+18V") (class "Default")
      (node (ref "D9") (pin "2") (pinfunction "K_2") (pintype "passive"))
      (node (ref "U10") (pin "1") (pinfunction "A_1") (pintype "passive"))
    )
    (net (code "64") (name "/X-18V") (class "Default")
      (node (ref "D13") (pin "2") (pinfunction "K_2") (pintype "passive"))
      (node (ref "U9") (pin "1") (pinfunction "A_1") (pintype "passive"))
    )
    (net (code "65") (name "/Y+18V") (class "Default")
      (node (ref "C5") (pin "1") (pinfunction "1_1") (pintype "passive"))
      (node (ref "R27") (pin "2") (pinfunction "2_2") (pintype "passive"))
      (node (ref "U10") (pin "2") (pinfunction "K_2") (pintype "passive"))
      (node (ref "U6") (pin "6") (pinfunction "IN-_6") (pintype "input"))
    )
    (net (code "66") (name "/Y-18V") (class "Default")
      (node (ref "R22") (pin "1") (pinfunction "1_1") (pintype "passive"))
      (node (ref "U9") (pin "2") (pinfunction "K_2") (pintype "passive"))
    )
    (net (code "67") (name "AGND") (class "Default")
      (node (ref "C15") (pin "1") (pinfunction "1_1") (pintype "passive"))
      (node (ref "C16") (pin "2") (pinfunction "2_2") (pintype "passive"))
      (node (ref "C5") (pin "2") (pinfunction "2_2") (pintype "passive"))
      (node (ref "D10") (pin "1") (pinfunction "A_1") (pintype "passive"))
      (node (ref "D12") (pin "2") (pinfunction "K_2") (pintype "passive"))
      (node (ref "D13") (pin "1") (pinfunction "A_1") (pintype "passive"))
      (node (ref "J6") (pin "1") (pinfunction "1_1") (pintype "passive"))
      (node (ref "P2") (pin "A3") (pinfunction "A3_A3") (pintype "passive"))
      (node (ref "P2") (pin "A4") (pinfunction "A4_A4") (pintype "passive"))
      (node (ref "P2") (pin "C3") (pinfunction "C3_C3") (pintype "passive"))
      (node (ref "P2") (pin "C4") (pinfunction "C4_C4") (pintype "passive"))
      (node (ref "P3") (pin "A3") (pinfunction "A3_A3") (pintype "passive"))
      (node (ref "P3") (pin "A4") (pinfunction "A4_A4") (pintype "passive"))
      (node (ref "P3") (pin "C3") (pinfunction "C3_C3") (pintype "passive"))
      (node (ref "P3") (pin "C4") (pinfunction "C4_C4") (pintype "passive"))
      (node (ref "R18") (pin "1") (pinfunction "1_1") (pintype "passive"))
      (node (ref "R19") (pin "1") (pinfunction "1_1") (pintype "passive"))
      (node (ref "R23") (pin "1") (pinfunction "1_1") (pintype "passive"))
      (node (ref "U6") (pin "4") (pinfunction "GND_4") (pintype "power_in"))
      (node (ref "U8") (pin "8") (pinfunction "V+_8") (pintype "power_in"))
      (node (ref "U9") (pin "3") (pinfunction "E_3") (pintype "passive"))
    )
    (net (code "68") (name "DGND") (class "Default")
      (node (ref "C10") (pin "1") (pinfunction "1_1") (pintype "passive"))
      (node (ref "C11") (pin "1") (pinfunction "1_1") (pintype "passive"))
      (node (ref "C12") (pin "1") (pinfunction "1_1") (pintype "passive"))
      (node (ref "C13") (pin "1") (pinfunction "1_1") (pintype "passive"))
      (node (ref "C14") (pin "1") (pinfunction "1_1") (pintype "passive"))
      (node (ref "C17") (pin "2") (pinfunction "2_2") (pintype "passive"))
      (node (ref "C18") (pin "2") (pinfunction "2_2") (pintype "passive"))
      (node (ref "C2") (pin "2") (pinfunction "2_2") (pintype "passive"))
      (node (ref "C3") (pin "2") (pinfunction "2_2") (pintype "passive"))
      (node (ref "C9") (pin "1") (pinfunction "1_1") (pintype "passive"))
      (node (ref "D14") (pin "1") (pinfunction "A_1") (pintype "passive"))
      (node (ref "D15") (pin "1") (pinfunction "A_1") (pintype "passive"))
      (node (ref "D16") (pin "1") (pinfunction "A_1") (pintype "passive"))
      (node (ref "D17") (pin "1") (pinfunction "A_1") (pintype "passive"))
      (node (ref "D18") (pin "1") (pinfunction "A_1") (pintype "passive"))
      (node (ref "D19") (pin "1") (pinfunction "A_1") (pintype "passive"))
      (node (ref "D20") (pin "1") (pinfunction "A_1") (pintype "passive"))
      (node (ref "D21") (pin "1") (pinfunction "A_1") (pintype "passive"))
      (node (ref "D22") (pin "1") (pinfunction "A_1") (pintype "passive"))
      (node (ref "D23") (pin "1") (pinfunction "A_1") (pintype "passive"))
      (node (ref "D24") (pin "1") (pinfunction "A_1") (pintype "passive"))
      (node (ref "D25") (pin "1") (pinfunction "A_1") (pintype "passive"))
      (node (ref "D26") (pin "1") (pinfunction "A_1") (pintype "passive"))
      (node (ref "D27") (pin "1") (pinfunction "A_1") (pintype "passive"))
      (node (ref "D28") (pin "1") (pinfunction "A_1") (pintype "passive"))
      (node (ref "D29") (pin "1") (pinfunction "A_1") (pintype "passive"))
      (node (ref "D3") (pin "1") (pinfunction "A_1") (pintype "passive"))
      (node (ref "D30") (pin "1") (pinfunction "A_1") (pintype "passive"))
      (node (ref "D31") (pin "1") (pinfunction "A_1") (pintype "passive"))
      (node (ref "D32") (pin "1") (pinfunction "A_1") (pintype "passive"))
      (node (ref "D33") (pin "1") (pinfunction "A_1") (pintype "passive"))
      (node (ref "D34") (pin "1") (pinfunction "A_1") (pintype "passive"))
      (node (ref "D35") (pin "1") (pinfunction "A_1") (pintype "passive"))
      (node (ref "D36") (pin "1") (pinfunction "A_1") (pintype "passive"))
      (node (ref "D37") (pin "1") (pinfunction "A_1") (pintype "passive"))
      (node (ref "D38") (pin "1") (pinfunction "A_1") (pintype "passive"))
      (node (ref "D39") (pin "1") (pinfunction "A_1") (pintype "passive"))
      (node (ref "D4") (pin "1") (pinfunction "A_1") (pintype "passive"))
      (node (ref "D40") (pin "1") (pinfunction "A_1") (pintype "passive"))
      (node (ref "D7") (pin "1") (pinfunction "A_1") (pintype "passive"))
      (node (ref "J2") (pin "1") (pinfunction "1_1") (pintype "passive"))
      (node (ref "J4") (pin "1") (pinfunction "1_1") (pintype "passive"))
      (node (ref "P1") (pin "10") (pinfunction "10_10") (pintype "passive"))
      (node (ref "P1") (pin "12") (pinfunction "12_12") (pintype "passive"))
      (node (ref "P1") (pin "14") (pinfunction "14_14") (pintype "passive"))
      (node (ref "P1") (pin "16") (pinfunction "16_16") (pintype "passive"))
      (node (ref "P1") (pin "2") (pinfunction "2_2") (pintype "passive"))
      (node (ref "P1") (pin "4") (pinfunction "4_4") (pintype "passive"))
      (node (ref "P1") (pin "6") (pinfunction "6_6") (pintype "passive"))
      (node (ref "P1") (pin "8") (pinfunction "8_8") (pintype "passive"))
      (node (ref "P2") (pin "A21") (pinfunction "A21_A21") (pintype "passive"))
      (node (ref "P2") (pin "A22") (pinfunction "A22_A22") (pintype "passive"))
      (node (ref "P2") (pin "A23") (pinfunction "A23_A23") (pintype "passive"))
      (node (ref "P2") (pin "A24") (pinfunction "A24_A24") (pintype "passive"))
      (node (ref "P2") (pin "A25") (pinfunction "A25_A25") (pintype "passive"))
      (node (ref "P2") (pin "A26") (pinfunction "A26_A26") (pintype "passive"))
      (node (ref "P2") (pin "A27") (pinfunction "A27_A27") (pintype "passive"))
      (node (ref "P2") (pin "A28") (pinfunction "A28_A28") (pintype "passive"))
      (node (ref "P2") (pin "A29") (pinfunction "A29_A29") (pintype "passive"))
      (node (ref "P2") (pin "A30") (pinfunction "A30_A30") (pintype "passive"))
      (node (ref "P2") (pin "A31") (pinfunction "A31_A31") (pintype "passive"))
      (node (ref "P2") (pin "A32") (pinfunction "A32_A32") (pintype "passive"))
      (node (ref "P3") (pin "A21") (pinfunction "A21_A21") (pintype "passive"))
      (node (ref "P3") (pin "A22") (pinfunction "A22_A22") (pintype "passive"))
      (node (ref "P3") (pin "A23") (pinfunction "A23_A23") (pintype "passive"))
      (node (ref "P3") (pin "A24") (pinfunction "A24_A24") (pintype "passive"))
      (node (ref "P3") (pin "A25") (pinfunction "A25_A25") (pintype "passive"))
      (node (ref "P3") (pin "A26") (pinfunction "A26_A26") (pintype "passive"))
      (node (ref "P3") (pin "A27") (pinfunction "A27_A27") (pintype "passive"))
      (node (ref "P3") (pin "A28") (pinfunction "A28_A28") (pintype "passive"))
      (node (ref "P3") (pin "A29") (pinfunction "A29_A29") (pintype "passive"))
      (node (ref "P3") (pin "A30") (pinfunction "A30_A30") (pintype "passive"))
      (node (ref "P3") (pin "A31") (pinfunction "A31_A31") (pintype "passive"))
      (node (ref "P3") (pin "A32") (pinfunction "A32_A32") (pintype "passive"))
      (node (ref "P4") (pin "10") (pinfunction "10_10") (pintype "passive"))
      (node (ref "P4") (pin "12") (pinfunction "12_12") (pintype "passive"))
      (node (ref "P4") (pin "14") (pinfunction "14_14") (pintype "passive"))
      (node (ref "P4") (pin "16") (pinfunction "16_16") (pintype "passive"))
      (node (ref "P4") (pin "18") (pinfunction "18_18") (pintype "passive"))
      (node (ref "P4") (pin "2") (pinfunction "2_2") (pintype "passive"))
      (node (ref "P4") (pin "20") (pinfunction "20_20") (pintype "passive"))
      (node (ref "P4") (pin "22") (pinfunction "22_22") (pintype "passive"))
      (node (ref "P4") (pin "24") (pinfunction "24_24") (pintype "passive"))
      (node (ref "P4") (pin "26") (pinfunction "26_26") (pintype "passive"))
      (node (ref "P4") (pin "28") (pinfunction "28_28") (pintype "passive"))
      (node (ref "P4") (pin "30") (pinfunction "30_30") (pintype "passive"))
      (node (ref "P4") (pin "32") (pinfunction "32_32") (pintype "passive"))
      (node (ref "P4") (pin "34") (pinfunction "34_34") (pintype "passive"))
      (node (ref "P4") (pin "36") (pinfunction "36_36") (pintype "passive"))
      (node (ref "P4") (pin "38") (pinfunction "38_38") (pintype "passive"))
      (node (ref "P4") (pin "4") (pinfunction "4_4") (pintype "passive"))
      (node (ref "P4") (pin "40") (pinfunction "40_40") (pintype "passive"))
      (node (ref "P4") (pin "42") (pinfunction "42_42") (pintype "passive"))
      (node (ref "P4") (pin "44") (pinfunction "44_44") (pintype "passive"))
      (node (ref "P4") (pin "46") (pinfunction "46_46") (pintype "passive"))
      (node (ref "P4") (pin "48") (pinfunction "48_48") (pintype "passive"))
      (node (ref "P4") (pin "50") (pinfunction "50_50") (pintype "passive"))
      (node (ref "P4") (pin "6") (pinfunction "6_6") (pintype "passive"))
      (node (ref "P4") (pin "8") (pinfunction "8_8") (pintype "passive"))
      (node (ref "R13") (pin "1") (pinfunction "1_1") (pintype "passive"))
      (node (ref "R7") (pin "1") (pinfunction "1_1") (pintype "passive"))
      (node (ref "U1") (pin "10") (pinfunction "GND_10") (pintype "power_in"))
      (node (ref "U1") (pin "19") (pinfunction "~{OE}_19") (pintype "input"))
      (node (ref "U2") (pin "4") (pinfunction "GND_4") (pintype "power_in"))
      (node (ref "U3") (pin "10") (pinfunction "GND_10") (pintype "power_in"))
      (node (ref "U3") (pin "19") (pinfunction "~{OE}_19") (pintype "input"))
      (node (ref "U4") (pin "4") (pinfunction "GND_4") (pintype "power_in"))
      (node (ref "U5") (pin "10") (pinfunction "GND_10") (pintype "power_in"))
      (node (ref "U5") (pin "19") (pinfunction "~{OE}_19") (pintype "input"))
      (node (ref "U7") (pin "10") (pinfunction "GND_10") (pintype "power_in"))
      (node (ref "U7") (pin "19") (pinfunction "~{OE}_19") (pintype "input"))
      (node (ref "W1") (pin "1") (pinfunction "C1_1") (pintype "passive"))
      (node (ref "W3") (pin "1") (pinfunction "C1_1") (pintype "passive"))
    )
    (net (code "69") (name "Net-(D1-A)") (class "Default")
      (node (ref "D1") (pin "1") (pinfunction "A_1") (pintype "passive"))
      (node (ref "R1") (pin "1") (pinfunction "1_1") (pintype "passive"))
    )
    (net (code "70") (name "Net-(D1-K)") (class "Default")
      (node (ref "C2") (pin "1") (pinfunction "1_1") (pintype "passive"))
      (node (ref "D1") (pin "2") (pinfunction "K_2") (pintype "passive"))
      (node (ref "R25") (pin "2") (pinfunction "2_2") (pintype "passive"))
      (node (ref "U2") (pin "6") (pinfunction "IN-_6") (pintype "input"))
    )
    (net (code "71") (name "Net-(D2-A)") (class "Default")
      (node (ref "D2") (pin "1") (pinfunction "A_1") (pintype "passive"))
      (node (ref "R3") (pin "1") (pinfunction "1_1") (pintype "passive"))
    )
    (net (code "72") (name "Net-(D2-K)") (class "Default")
      (node (ref "D2") (pin "2") (pinfunction "K_2") (pintype "passive"))
      (node (ref "D3") (pin "2") (pinfunction "K_2") (pintype "passive"))
    )
    (net (code "73") (name "Net-(D4-K)") (class "Default")
      (node (ref "C1") (pin "1") (pinfunction "1_1") (pintype "passive"))
      (node (ref "D4") (pin "2") (pinfunction "K_2") (pintype "passive"))
      (node (ref "R5") (pin "1") (pinfunction "1_1") (pintype "passive"))
      (node (ref "U2") (pin "3") (pinfunction "IN+_3") (pintype "input"))
      (node (ref "U2") (pin "5") (pinfunction "IN+_5") (pintype "input"))
    )
    (net (code "74") (name "Net-(D5-K)") (class "Default")
      (node (ref "D5") (pin "2") (pinfunction "K_2") (pintype "passive"))
      (node (ref "R11") (pin "2") (pinfunction "2_2") (pintype "passive"))
    )
    (net (code "75") (name "Net-(D6-A)") (class "Default")
      (node (ref "D6") (pin "1") (pinfunction "A_1") (pintype "passive"))
      (node (ref "R8") (pin "1") (pinfunction "1_1") (pintype "passive"))
    )
    (net (code "76") (name "Net-(D6-K)") (class "Default")
      (node (ref "C3") (pin "1") (pinfunction "1_1") (pintype "passive"))
      (node (ref "D6") (pin "2") (pinfunction "K_2") (pintype "passive"))
      (node (ref "R26") (pin "2") (pinfunction "2_2") (pintype "passive"))
      (node (ref "U4") (pin "6") (pinfunction "IN-_6") (pintype "input"))
    )
    (net (code "77") (name "Net-(D7-K)") (class "Default")
      (node (ref "D7") (pin "2") (pinfunction "K_2") (pintype "passive"))
      (node (ref "R11") (pin "1") (pinfunction "1_1") (pintype "passive"))
    )
    (net (code "78") (name "Net-(D8-K)") (class "Default")
      (node (ref "D8") (pin "2") (pinfunction "K_2") (pintype "passive"))
      (node (ref "R17") (pin "1") (pinfunction "1_1") (pintype "passive"))
    )
    (net (code "79") (name "Net-(D9-A)") (class "Default")
      (node (ref "D9") (pin "1") (pinfunction "A_1") (pintype "passive"))
      (node (ref "R15") (pin "1") (pinfunction "1_1") (pintype "passive"))
    )
    (net (code "80") (name "Net-(D10-K)") (class "Default")
      (node (ref "D10") (pin "2") (pinfunction "K_2") (pintype "passive"))
      (node (ref "R17") (pin "2") (pinfunction "2_2") (pintype "passive"))
    )
    (net (code "81") (name "Net-(D11-A)") (class "Default")
      (node (ref "D11") (pin "1") (pinfunction "A_1") (pintype "passive"))
      (node (ref "D12") (pin "1") (pinfunction "A_1") (pintype "passive"))
    )
    (net (code "82") (name "Net-(D11-K)") (class "Default")
      (node (ref "D11") (pin "2") (pinfunction "K_2") (pintype "passive"))
      (node (ref "R21") (pin "2") (pinfunction "2_2") (pintype "passive"))
    )
    (net (code "83") (name "Net-(Q1-G)") (class "Default")
      (node (ref "Q1") (pin "4") (pinfunction "G_4") (pintype "passive"))
      (node (ref "R2") (pin "1") (pinfunction "1_1") (pintype "passive"))
      (node (ref "U2") (pin "7") (pinfunction "OUT_7") (pintype "output"))
    )
    (net (code "84") (name "Net-(Q2-G)") (class "Default")
      (node (ref "Q2") (pin "4") (pinfunction "G_4") (pintype "passive"))
      (node (ref "R9") (pin "1") (pinfunction "1_1") (pintype "passive"))
      (node (ref "U4") (pin "7") (pinfunction "OUT_7") (pintype "output"))
    )
    (net (code "85") (name "Net-(Q3-G)") (class "Default")
      (node (ref "Q3") (pin "4") (pinfunction "G_4") (pintype "passive"))
      (node (ref "Q5") (pin "3") (pinfunction "C_3") (pintype "passive"))
      (node (ref "R16") (pin "1") (pinfunction "1_1") (pintype "passive"))
    )
    (net (code "86") (name "Net-(Q4-G)") (class "Default")
      (node (ref "Q4") (pin "4") (pinfunction "G_4") (pintype "passive"))
      (node (ref "R19") (pin "2") (pinfunction "2_2") (pintype "passive"))
      (node (ref "U10") (pin "4") (pinfunction "C_4") (pintype "passive"))
      (node (ref "U8") (pin "1") (pinfunction "OUT_1") (pintype "output"))
    )
    (net (code "87") (name "Net-(Q5-B)") (class "Default")
      (node (ref "Q5") (pin "1") (pinfunction "B_1") (pintype "passive"))
      (node (ref "R24") (pin "2") (pinfunction "2_2") (pintype "passive"))
      (node (ref "U9") (pin "4") (pinfunction "C_4") (pintype "passive"))
    )
    (net (code "88") (name "Net-(Q5-E)") (class "Default")
      (node (ref "Q5") (pin "2") (pinfunction "E_2") (pintype "passive"))
      (node (ref "U6") (pin "7") (pinfunction "OUT_7") (pintype "output"))
    )
    (net (code "89") (name "Net-(U2A-IN-)") (class "Default")
      (node (ref "C1") (pin "2") (pinfunction "2_2") (pintype "passive"))
      (node (ref "R4") (pin "1") (pinfunction "1_1") (pintype "passive"))
      (node (ref "R7") (pin "2") (pinfunction "2_2") (pintype "passive"))
      (node (ref "U2") (pin "2") (pinfunction "IN-_2") (pintype "input"))
    )
    (net (code "90") (name "Net-(U2A-OUT)") (class "Default")
      (node (ref "R25") (pin "1") (pinfunction "1_1") (pintype "passive"))
      (node (ref "U2") (pin "1") (pinfunction "OUT_1") (pintype "output"))
    )
    (net (code "91") (name "Net-(U4A-IN+)") (class "Default")
      (node (ref "C4") (pin "1") (pinfunction "1_1") (pintype "passive"))
      (node (ref "U4") (pin "3") (pinfunction "IN+_3") (pintype "input"))
      (node (ref "U4") (pin "5") (pinfunction "IN+_5") (pintype "input"))
    )
    (net (code "92") (name "Net-(U4A-IN-)") (class "Default")
      (node (ref "C4") (pin "2") (pinfunction "2_2") (pintype "passive"))
      (node (ref "R10") (pin "1") (pinfunction "1_1") (pintype "passive"))
      (node (ref "R13") (pin "2") (pinfunction "2_2") (pintype "passive"))
      (node (ref "U4") (pin "2") (pinfunction "IN-_2") (pintype "input"))
    )
    (net (code "93") (name "Net-(U4A-OUT)") (class "Default")
      (node (ref "R26") (pin "1") (pinfunction "1_1") (pintype "passive"))
      (node (ref "U4") (pin "1") (pinfunction "OUT_1") (pintype "output"))
    )
    (net (code "94") (name "Net-(U5-T{slash}~{R})") (class "Default")
      (node (ref "R12") (pin "1") (pinfunction "1_1") (pintype "passive"))
      (node (ref "U5") (pin "1") (pinfunction "T/~{R}_1") (pintype "input"))
      (node (ref "U7") (pin "1") (pinfunction "T/~{R}_1") (pintype "input"))
      (node (ref "W3") (pin "2") (pinfunction "C2_2") (pintype "passive"))
    )
    (net (code "95") (name "Net-(U6A-IN+)") (class "Default")
      (node (ref "C6") (pin "1") (pinfunction "1_1") (pintype "passive"))
      (node (ref "U6") (pin "3") (pinfunction "IN+_3") (pintype "input"))
      (node (ref "U6") (pin "5") (pinfunction "IN+_5") (pintype "input"))
    )
    (net (code "96") (name "Net-(U6A-IN-)") (class "Default")
      (node (ref "C6") (pin "2") (pinfunction "2_2") (pintype "passive"))
      (node (ref "R14") (pin "1") (pinfunction "1_1") (pintype "passive"))
      (node (ref "R18") (pin "2") (pinfunction "2_2") (pintype "passive"))
      (node (ref "U6") (pin "2") (pinfunction "IN-_2") (pintype "input"))
    )
    (net (code "97") (name "Net-(U6A-OUT)") (class "Default")
      (node (ref "R27") (pin "1") (pinfunction "1_1") (pintype "passive"))
      (node (ref "U6") (pin "1") (pinfunction "OUT_1") (pintype "output"))
    )
    (net (code "98") (name "Net-(U7-A1)") (class "Default")
      (node (ref "U7") (pin "3") (pinfunction "A1_3") (pintype "bidirectional"))
      (node (ref "W2") (pin "1") (pinfunction "C1_1") (pintype "passive"))
    )
    (net (code "99") (name "Net-(U8A-IN+)") (class "Default")
      (node (ref "C7") (pin "1") (pinfunction "1_1") (pintype "passive"))
      (node (ref "R22") (pin "2") (pinfunction "2_2") (pintype "passive"))
      (node (ref "R28") (pin "2") (pinfunction "2_2") (pintype "passive"))
      (node (ref "U8") (pin "3") (pinfunction "IN+_3") (pintype "input"))
    )
    (net (code "100") (name "Net-(U8A-IN-)") (class "Default")
      (node (ref "C8") (pin "1") (pinfunction "1_1") (pintype "passive"))
      (node (ref "U8") (pin "2") (pinfunction "IN-_2") (pintype "input"))
      (node (ref "U8") (pin "6") (pinfunction "IN-_6") (pintype "input"))
    )
    (net (code "101") (name "Net-(U8B-IN+)") (class "Default")
      (node (ref "C8") (pin "2") (pinfunction "2_2") (pintype "passive"))
      (node (ref "R20") (pin "1") (pinfunction "1_1") (pintype "passive"))
      (node (ref "R23") (pin "2") (pinfunction "2_2") (pintype "passive"))
      (node (ref "U8") (pin "5") (pinfunction "IN+_5") (pintype "input"))
    )
    (net (code "102") (name "Net-(U8B-OUT)") (class "Default")
      (node (ref "R28") (pin "1") (pinfunction "1_1") (pintype "passive"))
      (node (ref "U8") (pin "7") (pinfunction "OUT_7") (pintype "output"))
    )
    (net (code "103") (name "unconnected-(P1-Pad3)") (class "Default")
      (node (ref "P1") (pin "3") (pinfunction "3_3") (pintype "passive"))
    )
    (net (code "104") (name "unconnected-(P1-Pad5)") (class "Default")
      (node (ref "P1") (pin "5") (pinfunction "5_5") (pintype "passive"))
    )
    (net (code "105") (name "unconnected-(P1-Pad7)") (class "Default")
      (node (ref "P1") (pin "7") (pinfunction "7_7") (pintype "passive"))
    )
    (net (code "106") (name "unconnected-(P1-Pad9)") (class "Default")
      (node (ref "P1") (pin "9") (pinfunction "9_9") (pintype "passive"))
    )
    (net (code "107") (name "unconnected-(P1-Pad11)") (class "Default")
      (node (ref "P1") (pin "11") (pinfunction "11_11") (pintype "passive"))
    )
    (net (code "108") (name "unconnected-(P1-Pad15)") (class "Default")
      (node (ref "P1") (pin "15") (pinfunction "15_15") (pintype "passive"))
    )
    (net (code "109") (name "unconnected-(P3-PadA1)") (class "Default")
      (node (ref "P3") (pin "A1") (pinfunction "A1_A1") (pintype "passive"))
    )
    (net (code "110") (name "unconnected-(P3-PadC1)") (class "Default")
      (node (ref "P3") (pin "C1") (pinfunction "C1_C1") (pintype "passive"))
    )
    (net (code "111") (name "unconnected-(P3-PadC7)") (class "Default")
      (node (ref "P3") (pin "C7") (pinfunction "C7_C7") (pintype "passive"))
    )
    (net (code "112") (name "unconnected-(P3-PadC9)") (class "Default")
      (node (ref "P3") (pin "C9") (pinfunction "C9_C9") (pintype "passive"))
    )
    (net (code "113") (name "unconnected-(P3-PadC10)") (class "Default")
      (node (ref "P3") (pin "C10") (pinfunction "C10_C10") (pintype "passive"))
    )
    (net (code "114") (name "unconnected-(P3-PadC11)") (class "Default")
      (node (ref "P3") (pin "C11") (pinfunction "C11_C11") (pintype "passive"))
    )
    (net (code "115") (name "unconnected-(P3-PadC12)") (class "Default")
      (node (ref "P3") (pin "C12") (pinfunction "C12_C12") (pintype "passive"))
    )
    (net (code "116") (name "unconnected-(P3-PadC13)") (class "Default")
      (node (ref "P3") (pin "C13") (pinfunction "C13_C13") (pintype "passive"))
    )
    (net (code "117") (name "unconnected-(P3-PadC14)") (class "Default")
      (node (ref "P3") (pin "C14") (pinfunction "C14_C14") (pintype "passive"))
    )
    (net (code "118") (name "unconnected-(P3-PadC15)") (class "Default")
      (node (ref "P3") (pin "C15") (pinfunction "C15_C15") (pintype "passive"))
    )
    (net (code "119") (name "unconnected-(P3-PadC16)") (class "Default")
      (node (ref "P3") (pin "C16") (pinfunction "C16_C16") (pintype "passive"))
    )
    (net (code "120") (name "unconnected-(P3-PadC17)") (class "Default")
      (node (ref "P3") (pin "C17") (pinfunction "C17_C17") (pintype "passive"))
    )
    (net (code "121") (name "unconnected-(P3-PadC18)") (class "Default")
      (node (ref "P3") (pin "C18") (pinfunction "C18_C18") (pintype "passive"))
    )
    (net (code "122") (name "unconnected-(P3-PadC19)") (class "Default")
      (node (ref "P3") (pin "C19") (pinfunction "C19_C19") (pintype "passive"))
    )
    (net (code "123") (name "unconnected-(P3-PadC20)") (class "Default")
      (node (ref "P3") (pin "C20") (pinfunction "C20_C20") (pintype "passive"))
    )
    (net (code "124") (name "unconnected-(P3-PadC21)") (class "Default")
      (node (ref "P3") (pin "C21") (pinfunction "C21_C21") (pintype "passive"))
    )
    (net (code "125") (name "unconnected-(P3-PadC22)") (class "Default")
      (node (ref "P3") (pin "C22") (pinfunction "C22_C22") (pintype "passive"))
    )
    (net (code "126") (name "unconnected-(P3-PadC23)") (class "Default")
      (node (ref "P3") (pin "C23") (pinfunction "C23_C23") (pintype "passive"))
    )
    (net (code "127") (name "unconnected-(P3-PadC24)") (class "Default")
      (node (ref "P3") (pin "C24") (pinfunction "C24_C24") (pintype "passive"))
    )
    (net (code "128") (name "unconnected-(P3-PadC25)") (class "Default")
      (node (ref "P3") (pin "C25") (pinfunction "C25_C25") (pintype "passive"))
    )
    (net (code "129") (name "unconnected-(P3-PadC26)") (class "Default")
      (node (ref "P3") (pin "C26") (pinfunction "C26_C26") (pintype "passive"))
    )
    (net (code "130") (name "unconnected-(P3-PadC27)") (class "Default")
      (node (ref "P3") (pin "C27") (pinfunction "C27_C27") (pintype "passive"))
    )
    (net (code "131") (name "unconnected-(P3-PadC28)") (class "Default")
      (node (ref "P3") (pin "C28") (pinfunction "C28_C28") (pintype "passive"))
    )
    (net (code "132") (name "unconnected-(P3-PadC29)") (class "Default")
      (node (ref "P3") (pin "C29") (pinfunction "C29_C29") (pintype "passive"))
    )
    (net (code "133") (name "unconnected-(P3-PadC30)") (class "Default")
      (node (ref "P3") (pin "C30") (pinfunction "C30_C30") (pintype "passive"))
    )
    (net (code "134") (name "unconnected-(P3-PadC31)") (class "Default")
      (node (ref "P3") (pin "C31") (pinfunction "C31_C31") (pintype "passive"))
    )
    (net (code "135") (name "unconnected-(P3-PadC32)") (class "Default")
      (node (ref "P3") (pin "C32") (pinfunction "C32_C32") (pintype "passive"))
    )
    (net (code "136") (name "unconnected-(U2B-GND-Pad4)") (class "Default")
      (node (ref "U2") (pin "4") (pinfunction "GND_4") (pintype "power_in"))
    )
    (net (code "137") (name "unconnected-(U2B-V+-Pad8)") (class "Default")
      (node (ref "U2") (pin "8") (pinfunction "V+_8") (pintype "power_in"))
    )
    (net (code "138") (name "unconnected-(U4B-GND-Pad4)") (class "Default")
      (node (ref "U4") (pin "4") (pinfunction "GND_4") (pintype "power_in"))
    )
    (net (code "139") (name "unconnected-(U4B-V+-Pad8)") (class "Default")
      (node (ref "U4") (pin "8") (pinfunction "V+_8") (pintype "power_in"))
    )
    (net (code "140") (name "unconnected-(U6B-GND-Pad4)") (class "Default")
      (node (ref "U6") (pin "4") (pinfunction "GND_4") (pintype "power_in"))
    )
    (net (code "141") (name "unconnected-(U6B-V+-Pad8)") (class "Default")
      (node (ref "U6") (pin "8") (pinfunction "V+_8") (pintype "power_in"))
    )
    (net (code "142") (name "unconnected-(U7-A2-Pad4)") (class "Default")
      (node (ref "U7") (pin "4") (pinfunction "A2_4") (pintype "bidirectional"))
    )
    (net (code "143") (name "unconnected-(U7-A3-Pad5)") (class "Default")
      (node (ref "U7") (pin "5") (pinfunction "A3_5") (pintype "bidirectional"))
    )
    (net (code "144") (name "unconnected-(U7-A4-Pad6)") (class "Default")
      (node (ref "U7") (pin "6") (pinfunction "A4_6") (pintype "bidirectional"))
    )
    (net (code "145") (name "unconnected-(U7-A5-Pad7)") (class "Default")
      (node (ref "U7") (pin "7") (pinfunction "A5_7") (pintype "bidirectional"))
    )
    (net (code "146") (name "unconnected-(U7-A6-Pad8)") (class "Default")
      (node (ref "U7") (pin "8") (pinfunction "A6_8") (pintype "bidirectional"))
    )
    (net (code "147") (name "unconnected-(U7-B2-Pad16)") (class "Default")
      (node (ref "U7") (pin "16") (pinfunction "B2_16") (pintype "bidirectional"))
    )
    (net (code "148") (name "unconnected-(U7-B3-Pad15)") (class "Default")
      (node (ref "U7") (pin "15") (pinfunction "B3_15") (pintype "bidirectional"))
    )
    (net (code "149") (name "unconnected-(U7-B4-Pad14)") (class "Default")
      (node (ref "U7") (pin "14") (pinfunction "B4_14") (pintype "bidirectional"))
    )
    (net (code "150") (name "unconnected-(U7-B5-Pad13)") (class "Default")
      (node (ref "U7") (pin "13") (pinfunction "B5_13") (pintype "bidirectional"))
    )
    (net (code "151") (name "unconnected-(U7-B6-Pad12)") (class "Default")
      (node (ref "U7") (pin "12") (pinfunction "B6_12") (pintype "bidirectional"))
    )
    (net (code "152") (name "unconnected-(U8A-GND-Pad4)") (class "Default")
      (node (ref "U8") (pin "4") (pinfunction "GND_4") (pintype "power_in"))
    )
    (net (code "153") (name "unconnected-(U8A-V+-Pad8)") (class "Default")
      (node (ref "U8") (pin "8") (pinfunction "V+_8") (pintype "power_in"))
    )
  )
)
